# USB_SATA.net
KiCad netlist of a schematic drawn in Altium Designer
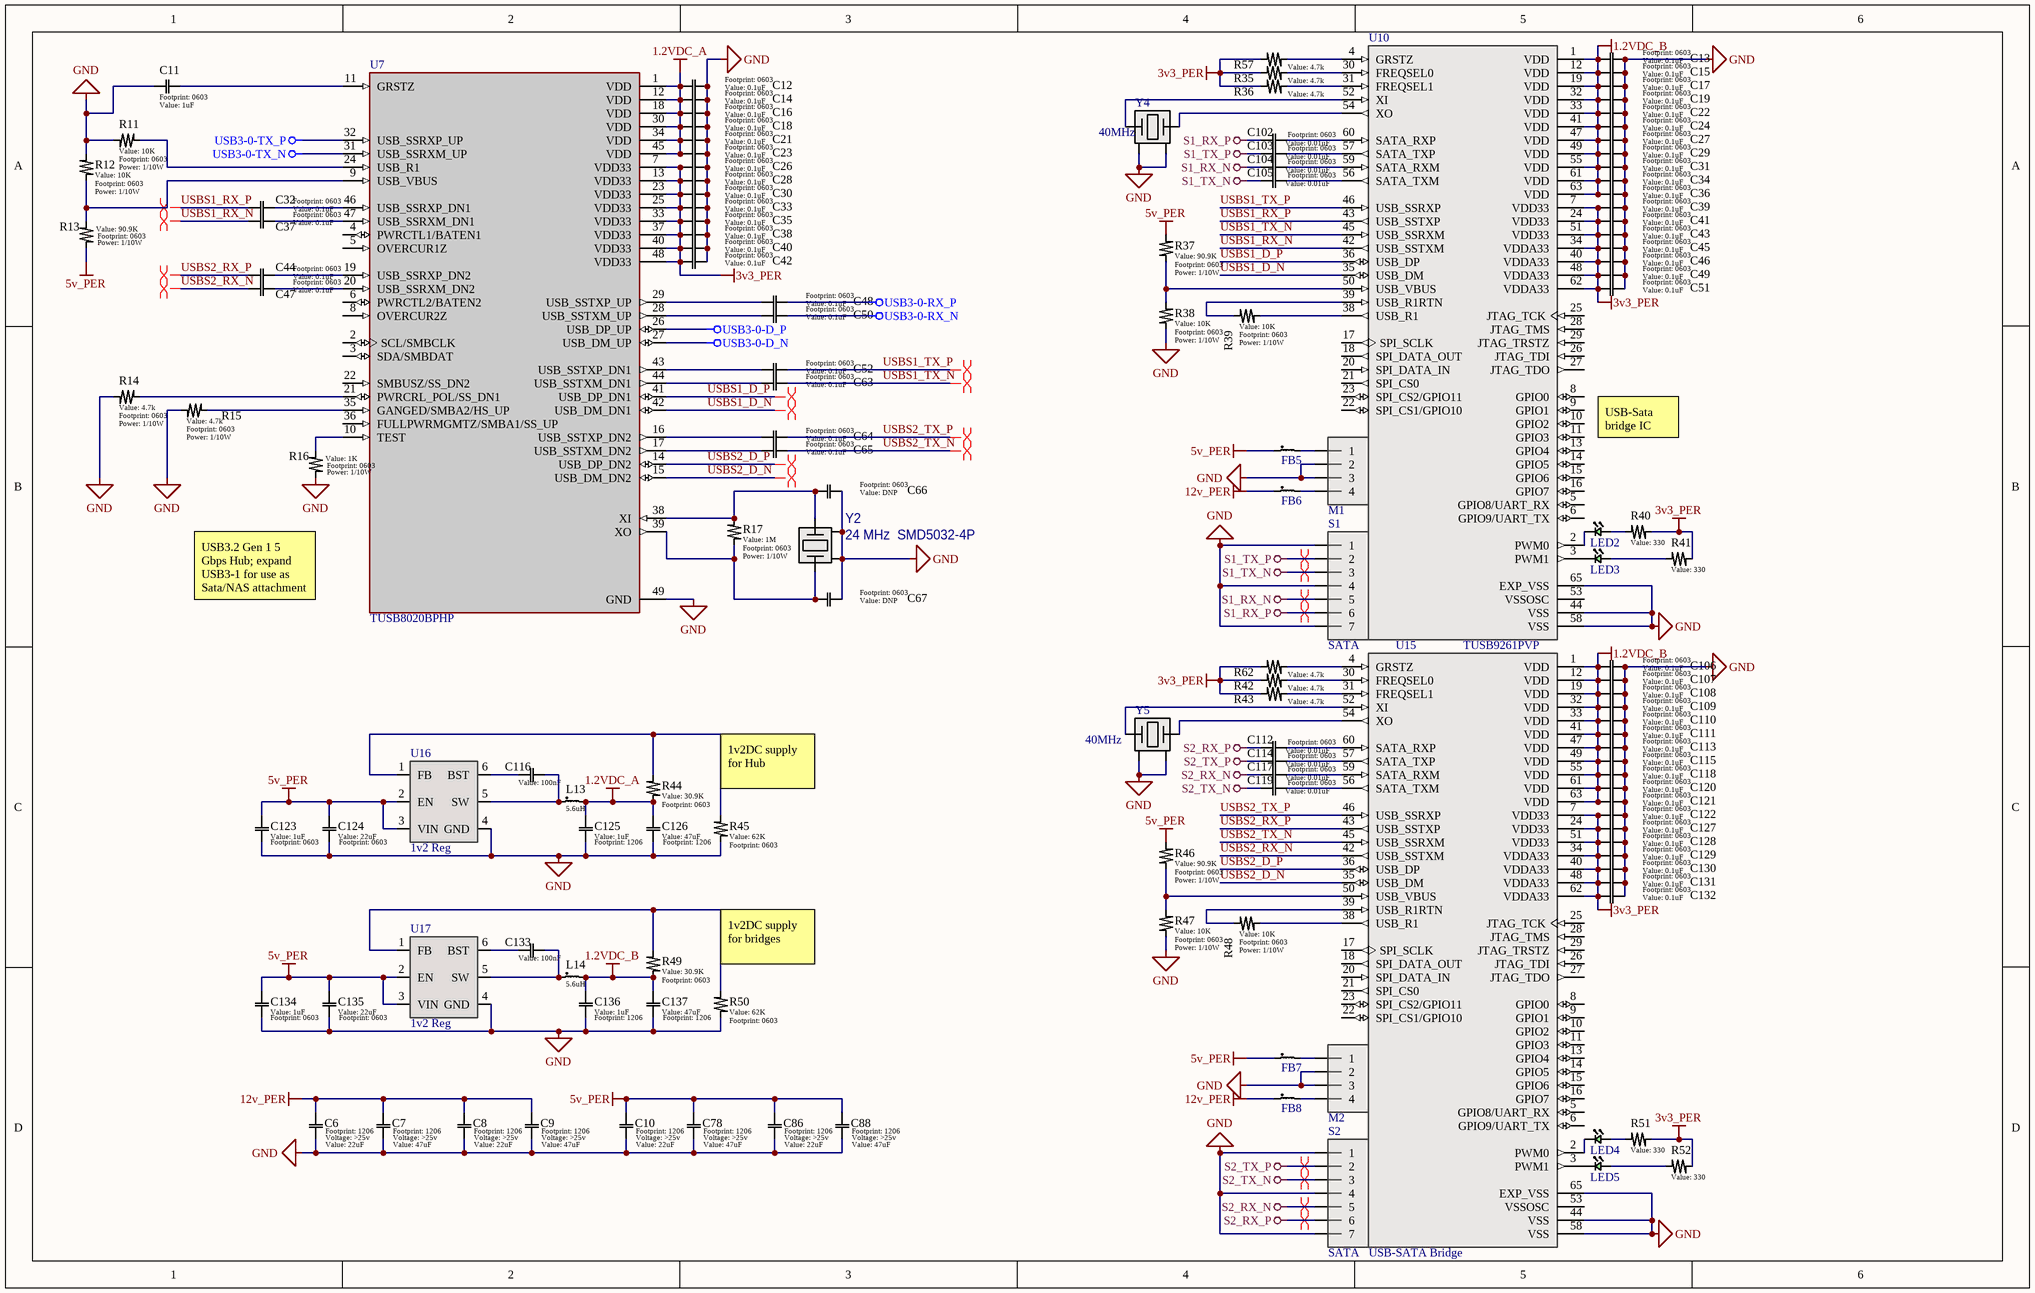
[diagram p0: USB_SATA.SchDoc]

(export (version "E")
  (design (tool "Eeschema 10.0.6"))
  (components
    (comp (ref "C6")
      (value "22uF")
      (footprint "1206")
      (fields
        (field (name "VOLTAGE") ">25v")
        (field (name "TOLERANCE") "20%")
        (field (name "Comment") "Generic Capacitor")
      )
      (libsource (lib "Capacitors") (part "Generic Capacitor"))
    )
    (comp (ref "C7")
      (value "47uF")
      (footprint "1206")
      (fields
        (field (name "VOLTAGE") ">25v")
        (field (name "TOLERANCE") "20%")
        (field (name "Comment") "Generic Capacitor")
      )
      (libsource (lib "Capacitors") (part "Generic Capacitor"))
    )
    (comp (ref "C8")
      (value "22uF")
      (footprint "1206")
      (fields
        (field (name "VOLTAGE") ">25v")
        (field (name "TOLERANCE") "20%")
        (field (name "Comment") "Generic Capacitor")
      )
      (libsource (lib "Capacitors") (part "Generic Capacitor"))
    )
    (comp (ref "C9")
      (value "47uF")
      (footprint "1206")
      (fields
        (field (name "VOLTAGE") ">25v")
        (field (name "TOLERANCE") "20%")
        (field (name "Comment") "Generic Capacitor")
      )
      (libsource (lib "Capacitors") (part "Generic Capacitor"))
    )
    (comp (ref "C10")
      (value "22uF")
      (footprint "1206")
      (fields
        (field (name "VOLTAGE") ">25v")
        (field (name "TOLERANCE") "20%")
        (field (name "Comment") "Generic Capacitor")
      )
      (libsource (lib "Capacitors") (part "Generic Capacitor"))
    )
    (comp (ref "C11")
      (value "1uF")
      (footprint "0603")
      (fields
        (field (name "VOLTAGE") ">10V")
        (field (name "TOLERANCE") "10%")
        (field (name "Comment") "Generic Capacitor")
      )
      (libsource (lib "Capacitors") (part "Generic Capacitor"))
    )
    (comp (ref "C12")
      (value "0.1uF")
      (footprint "0603")
      (fields
        (field (name "VOLTAGE") "10V")
        (field (name "TOLERANCE") "10%")
        (field (name "Comment") "Generic Capacitor")
      )
      (libsource (lib "Capacitors") (part "Generic Capacitor"))
    )
    (comp (ref "C13")
      (value "0.1uF")
      (footprint "0603")
      (fields
        (field (name "VOLTAGE") "10V")
        (field (name "TOLERANCE") "10%")
        (field (name "Comment") "Generic Capacitor")
      )
      (libsource (lib "Capacitors") (part "Generic Capacitor"))
    )
    (comp (ref "C14")
      (value "0.1uF")
      (footprint "0603")
      (fields
        (field (name "VOLTAGE") "10V")
        (field (name "TOLERANCE") "10%")
        (field (name "Comment") "Generic Capacitor")
      )
      (libsource (lib "Capacitors") (part "Generic Capacitor"))
    )
    (comp (ref "C15")
      (value "0.1uF")
      (footprint "0603")
      (fields
        (field (name "VOLTAGE") "10V")
        (field (name "TOLERANCE") "10%")
        (field (name "Comment") "Generic Capacitor")
      )
      (libsource (lib "Capacitors") (part "Generic Capacitor"))
    )
    (comp (ref "C16")
      (value "0.1uF")
      (footprint "0603")
      (fields
        (field (name "VOLTAGE") "10V")
        (field (name "TOLERANCE") "10%")
        (field (name "Comment") "Generic Capacitor")
      )
      (libsource (lib "Capacitors") (part "Generic Capacitor"))
    )
    (comp (ref "C17")
      (value "0.1uF")
      (footprint "0603")
      (fields
        (field (name "VOLTAGE") "10V")
        (field (name "TOLERANCE") "10%")
        (field (name "Comment") "Generic Capacitor")
      )
      (libsource (lib "Capacitors") (part "Generic Capacitor"))
    )
    (comp (ref "C18")
      (value "0.1uF")
      (footprint "0603")
      (fields
        (field (name "VOLTAGE") "10V")
        (field (name "TOLERANCE") "10%")
        (field (name "Comment") "Generic Capacitor")
      )
      (libsource (lib "Capacitors") (part "Generic Capacitor"))
    )
    (comp (ref "C19")
      (value "0.1uF")
      (footprint "0603")
      (fields
        (field (name "VOLTAGE") "10V")
        (field (name "TOLERANCE") "10%")
        (field (name "Comment") "Generic Capacitor")
      )
      (libsource (lib "Capacitors") (part "Generic Capacitor"))
    )
    (comp (ref "C21")
      (value "0.1uF")
      (footprint "0603")
      (fields
        (field (name "VOLTAGE") "10V")
        (field (name "TOLERANCE") "10%")
        (field (name "Comment") "Generic Capacitor")
      )
      (libsource (lib "Capacitors") (part "Generic Capacitor"))
    )
    (comp (ref "C22")
      (value "0.1uF")
      (footprint "0603")
      (fields
        (field (name "VOLTAGE") "10V")
        (field (name "TOLERANCE") "10%")
        (field (name "Comment") "Generic Capacitor")
      )
      (libsource (lib "Capacitors") (part "Generic Capacitor"))
    )
    (comp (ref "C23")
      (value "0.1uF")
      (footprint "0603")
      (fields
        (field (name "VOLTAGE") "10V")
        (field (name "TOLERANCE") "10%")
        (field (name "Comment") "Generic Capacitor")
      )
      (libsource (lib "Capacitors") (part "Generic Capacitor"))
    )
    (comp (ref "C24")
      (value "0.1uF")
      (footprint "0603")
      (fields
        (field (name "VOLTAGE") "10V")
        (field (name "TOLERANCE") "10%")
        (field (name "Comment") "Generic Capacitor")
      )
      (libsource (lib "Capacitors") (part "Generic Capacitor"))
    )
    (comp (ref "C26")
      (value "0.1uF")
      (footprint "0603")
      (fields
        (field (name "VOLTAGE") "10V")
        (field (name "TOLERANCE") "10%")
        (field (name "Comment") "Generic Capacitor")
      )
      (libsource (lib "Capacitors") (part "Generic Capacitor"))
    )
    (comp (ref "C27")
      (value "0.1uF")
      (footprint "0603")
      (fields
        (field (name "VOLTAGE") "10V")
        (field (name "TOLERANCE") "10%")
        (field (name "Comment") "Generic Capacitor")
      )
      (libsource (lib "Capacitors") (part "Generic Capacitor"))
    )
    (comp (ref "C28")
      (value "0.1uF")
      (footprint "0603")
      (fields
        (field (name "VOLTAGE") "10V")
        (field (name "TOLERANCE") "10%")
        (field (name "Comment") "Generic Capacitor")
      )
      (libsource (lib "Capacitors") (part "Generic Capacitor"))
    )
    (comp (ref "C29")
      (value "0.1uF")
      (footprint "0603")
      (fields
        (field (name "VOLTAGE") "10V")
        (field (name "TOLERANCE") "10%")
        (field (name "Comment") "Generic Capacitor")
      )
      (libsource (lib "Capacitors") (part "Generic Capacitor"))
    )
    (comp (ref "C30")
      (value "0.1uF")
      (footprint "0603")
      (fields
        (field (name "VOLTAGE") "10V")
        (field (name "TOLERANCE") "10%")
        (field (name "Comment") "Generic Capacitor")
      )
      (libsource (lib "Capacitors") (part "Generic Capacitor"))
    )
    (comp (ref "C31")
      (value "0.1uF")
      (footprint "0603")
      (fields
        (field (name "VOLTAGE") "10V")
        (field (name "TOLERANCE") "10%")
        (field (name "Comment") "Generic Capacitor")
      )
      (libsource (lib "Capacitors") (part "Generic Capacitor"))
    )
    (comp (ref "C32")
      (value "0.1uF")
      (footprint "0603")
      (fields
        (field (name "VOLTAGE") "10V")
        (field (name "TOLERANCE") "10%")
        (field (name "Comment") "Generic Capacitor")
      )
      (libsource (lib "Capacitors") (part "Generic Capacitor"))
    )
    (comp (ref "C33")
      (value "0.1uF")
      (footprint "0603")
      (fields
        (field (name "VOLTAGE") "10V")
        (field (name "TOLERANCE") "10%")
        (field (name "Comment") "Generic Capacitor")
      )
      (libsource (lib "Capacitors") (part "Generic Capacitor"))
    )
    (comp (ref "C34")
      (value "0.1uF")
      (footprint "0603")
      (fields
        (field (name "VOLTAGE") "10V")
        (field (name "TOLERANCE") "10%")
        (field (name "Comment") "Generic Capacitor")
      )
      (libsource (lib "Capacitors") (part "Generic Capacitor"))
    )
    (comp (ref "C35")
      (value "0.1uF")
      (footprint "0603")
      (fields
        (field (name "VOLTAGE") "10V")
        (field (name "TOLERANCE") "10%")
        (field (name "Comment") "Generic Capacitor")
      )
      (libsource (lib "Capacitors") (part "Generic Capacitor"))
    )
    (comp (ref "C36")
      (value "0.1uF")
      (footprint "0603")
      (fields
        (field (name "VOLTAGE") "10V")
        (field (name "TOLERANCE") "10%")
        (field (name "Comment") "Generic Capacitor")
      )
      (libsource (lib "Capacitors") (part "Generic Capacitor"))
    )
    (comp (ref "C37")
      (value "0.1uF")
      (footprint "0603")
      (fields
        (field (name "VOLTAGE") "10V")
        (field (name "TOLERANCE") "10%")
        (field (name "Comment") "Generic Capacitor")
      )
      (libsource (lib "Capacitors") (part "Generic Capacitor"))
    )
    (comp (ref "C38")
      (value "0.1uF")
      (footprint "0603")
      (fields
        (field (name "VOLTAGE") "10V")
        (field (name "TOLERANCE") "10%")
        (field (name "Comment") "Generic Capacitor")
      )
      (libsource (lib "Capacitors") (part "Generic Capacitor"))
    )
    (comp (ref "C39")
      (value "0.1uF")
      (footprint "0603")
      (fields
        (field (name "VOLTAGE") "10V")
        (field (name "TOLERANCE") "10%")
        (field (name "Comment") "Generic Capacitor")
      )
      (libsource (lib "Capacitors") (part "Generic Capacitor"))
    )
    (comp (ref "C40")
      (value "0.1uF")
      (footprint "0603")
      (fields
        (field (name "VOLTAGE") "10V")
        (field (name "TOLERANCE") "10%")
        (field (name "Comment") "Generic Capacitor")
      )
      (libsource (lib "Capacitors") (part "Generic Capacitor"))
    )
    (comp (ref "C41")
      (value "0.1uF")
      (footprint "0603")
      (fields
        (field (name "VOLTAGE") "10V")
        (field (name "TOLERANCE") "10%")
        (field (name "Comment") "Generic Capacitor")
      )
      (libsource (lib "Capacitors") (part "Generic Capacitor"))
    )
    (comp (ref "C42")
      (value "0.1uF")
      (footprint "0603")
      (fields
        (field (name "VOLTAGE") "10V")
        (field (name "TOLERANCE") "10%")
        (field (name "Comment") "Generic Capacitor")
      )
      (libsource (lib "Capacitors") (part "Generic Capacitor"))
    )
    (comp (ref "C43")
      (value "0.1uF")
      (footprint "0603")
      (fields
        (field (name "VOLTAGE") "10V")
        (field (name "TOLERANCE") "10%")
        (field (name "Comment") "Generic Capacitor")
      )
      (libsource (lib "Capacitors") (part "Generic Capacitor"))
    )
    (comp (ref "C44")
      (value "0.1uF")
      (footprint "0603")
      (fields
        (field (name "VOLTAGE") "10V")
        (field (name "TOLERANCE") "10%")
        (field (name "Comment") "Generic Capacitor")
      )
      (libsource (lib "Capacitors") (part "Generic Capacitor"))
    )
    (comp (ref "C45")
      (value "0.1uF")
      (footprint "0603")
      (fields
        (field (name "VOLTAGE") "10V")
        (field (name "TOLERANCE") "10%")
        (field (name "Comment") "Generic Capacitor")
      )
      (libsource (lib "Capacitors") (part "Generic Capacitor"))
    )
    (comp (ref "C46")
      (value "0.1uF")
      (footprint "0603")
      (fields
        (field (name "VOLTAGE") "10V")
        (field (name "TOLERANCE") "10%")
        (field (name "Comment") "Generic Capacitor")
      )
      (libsource (lib "Capacitors") (part "Generic Capacitor"))
    )
    (comp (ref "C47")
      (value "0.1uF")
      (footprint "0603")
      (fields
        (field (name "VOLTAGE") "10V")
        (field (name "TOLERANCE") "10%")
        (field (name "Comment") "Generic Capacitor")
      )
      (libsource (lib "Capacitors") (part "Generic Capacitor"))
    )
    (comp (ref "C48")
      (value "0.1uF")
      (footprint "0603")
      (fields
        (field (name "VOLTAGE") "10V")
        (field (name "TOLERANCE") "10%")
        (field (name "Comment") "Generic Capacitor")
      )
      (libsource (lib "Capacitors") (part "Generic Capacitor"))
    )
    (comp (ref "C49")
      (value "0.1uF")
      (footprint "0603")
      (fields
        (field (name "VOLTAGE") "10V")
        (field (name "TOLERANCE") "10%")
        (field (name "Comment") "Generic Capacitor")
      )
      (libsource (lib "Capacitors") (part "Generic Capacitor"))
    )
    (comp (ref "C50")
      (value "0.1uF")
      (footprint "0603")
      (fields
        (field (name "VOLTAGE") "10V")
        (field (name "TOLERANCE") "10%")
        (field (name "Comment") "Generic Capacitor")
      )
      (libsource (lib "Capacitors") (part "Generic Capacitor"))
    )
    (comp (ref "C51")
      (value "0.1uF")
      (footprint "0603")
      (fields
        (field (name "VOLTAGE") "10V")
        (field (name "TOLERANCE") "10%")
        (field (name "Comment") "Generic Capacitor")
      )
      (libsource (lib "Capacitors") (part "Generic Capacitor"))
    )
    (comp (ref "C52")
      (value "0.1uF")
      (footprint "0603")
      (fields
        (field (name "VOLTAGE") "10V")
        (field (name "TOLERANCE") "10%")
        (field (name "Comment") "Generic Capacitor")
      )
      (libsource (lib "Capacitors") (part "Generic Capacitor"))
    )
    (comp (ref "C63")
      (value "0.1uF")
      (footprint "0603")
      (fields
        (field (name "VOLTAGE") "10V")
        (field (name "TOLERANCE") "10%")
        (field (name "Comment") "Generic Capacitor")
      )
      (libsource (lib "Capacitors") (part "Generic Capacitor"))
    )
    (comp (ref "C64")
      (value "0.1uF")
      (footprint "0603")
      (fields
        (field (name "VOLTAGE") "10V")
        (field (name "TOLERANCE") "10%")
        (field (name "Comment") "Generic Capacitor")
      )
      (libsource (lib "Capacitors") (part "Generic Capacitor"))
    )
    (comp (ref "C65")
      (value "0.1uF")
      (footprint "0603")
      (fields
        (field (name "VOLTAGE") "10V")
        (field (name "TOLERANCE") "10%")
        (field (name "Comment") "Generic Capacitor")
      )
      (libsource (lib "Capacitors") (part "Generic Capacitor"))
    )
    (comp (ref "C66")
      (value "DNP")
      (footprint "0603")
      (fields
        (field (name "VOLTAGE") ">10V")
        (field (name "TOLERANCE") "10%")
        (field (name "Comment") "Generic Capacitor")
      )
      (libsource (lib "Capacitors") (part "Generic Capacitor"))
    )
    (comp (ref "C67")
      (value "DNP")
      (footprint "0603")
      (fields
        (field (name "VOLTAGE") ">10V")
        (field (name "TOLERANCE") "10%")
        (field (name "Comment") "Generic Capacitor")
      )
      (libsource (lib "Capacitors") (part "Generic Capacitor"))
    )
    (comp (ref "C78")
      (value "47uF")
      (footprint "1206")
      (fields
        (field (name "VOLTAGE") ">25v")
        (field (name "TOLERANCE") "20%")
        (field (name "Comment") "Generic Capacitor")
      )
      (libsource (lib "Capacitors") (part "Generic Capacitor"))
    )
    (comp (ref "C86")
      (value "22uF")
      (footprint "1206")
      (fields
        (field (name "VOLTAGE") ">25v")
        (field (name "TOLERANCE") "20%")
        (field (name "Comment") "Generic Capacitor")
      )
      (libsource (lib "Capacitors") (part "Generic Capacitor"))
    )
    (comp (ref "C88")
      (value "47uF")
      (footprint "1206")
      (fields
        (field (name "VOLTAGE") ">25v")
        (field (name "TOLERANCE") "20%")
        (field (name "Comment") "Generic Capacitor")
      )
      (libsource (lib "Capacitors") (part "Generic Capacitor"))
    )
    (comp (ref "C102")
      (value "0.01uF")
      (footprint "0603")
      (fields
        (field (name "VOLTAGE") "10V")
        (field (name "TOLERANCE") "10%")
        (field (name "Comment") "Generic Capacitor")
      )
      (libsource (lib "Capacitors") (part "Generic Capacitor"))
    )
    (comp (ref "C103")
      (value "0.01uF")
      (footprint "0603")
      (fields
        (field (name "VOLTAGE") "10V")
        (field (name "TOLERANCE") "10%")
        (field (name "Comment") "Generic Capacitor")
      )
      (libsource (lib "Capacitors") (part "Generic Capacitor"))
    )
    (comp (ref "C104")
      (value "0.01uF")
      (footprint "0603")
      (fields
        (field (name "VOLTAGE") "10V")
        (field (name "TOLERANCE") "10%")
        (field (name "Comment") "Generic Capacitor")
      )
      (libsource (lib "Capacitors") (part "Generic Capacitor"))
    )
    (comp (ref "C105")
      (value "0.01uF")
      (footprint "0603")
      (fields
        (field (name "VOLTAGE") "10V")
        (field (name "TOLERANCE") "10%")
        (field (name "Comment") "Generic Capacitor")
      )
      (libsource (lib "Capacitors") (part "Generic Capacitor"))
    )
    (comp (ref "C106")
      (value "0.1uF")
      (footprint "0603")
      (fields
        (field (name "VOLTAGE") "10V")
        (field (name "TOLERANCE") "10%")
        (field (name "Comment") "Generic Capacitor")
      )
      (libsource (lib "Capacitors") (part "Generic Capacitor"))
    )
    (comp (ref "C107")
      (value "0.1uF")
      (footprint "0603")
      (fields
        (field (name "VOLTAGE") "10V")
        (field (name "TOLERANCE") "10%")
        (field (name "Comment") "Generic Capacitor")
      )
      (libsource (lib "Capacitors") (part "Generic Capacitor"))
    )
    (comp (ref "C108")
      (value "0.1uF")
      (footprint "0603")
      (fields
        (field (name "VOLTAGE") "10V")
        (field (name "TOLERANCE") "10%")
        (field (name "Comment") "Generic Capacitor")
      )
      (libsource (lib "Capacitors") (part "Generic Capacitor"))
    )
    (comp (ref "C109")
      (value "0.1uF")
      (footprint "0603")
      (fields
        (field (name "VOLTAGE") "10V")
        (field (name "TOLERANCE") "10%")
        (field (name "Comment") "Generic Capacitor")
      )
      (libsource (lib "Capacitors") (part "Generic Capacitor"))
    )
    (comp (ref "C110")
      (value "0.1uF")
      (footprint "0603")
      (fields
        (field (name "VOLTAGE") "10V")
        (field (name "TOLERANCE") "10%")
        (field (name "Comment") "Generic Capacitor")
      )
      (libsource (lib "Capacitors") (part "Generic Capacitor"))
    )
    (comp (ref "C111")
      (value "0.1uF")
      (footprint "0603")
      (fields
        (field (name "VOLTAGE") "10V")
        (field (name "TOLERANCE") "10%")
        (field (name "Comment") "Generic Capacitor")
      )
      (libsource (lib "Capacitors") (part "Generic Capacitor"))
    )
    (comp (ref "C112")
      (value "0.01uF")
      (footprint "0603")
      (fields
        (field (name "VOLTAGE") "10V")
        (field (name "TOLERANCE") "10%")
        (field (name "Comment") "Generic Capacitor")
      )
      (libsource (lib "Capacitors") (part "Generic Capacitor"))
    )
    (comp (ref "C113")
      (value "0.1uF")
      (footprint "0603")
      (fields
        (field (name "VOLTAGE") "10V")
        (field (name "TOLERANCE") "10%")
        (field (name "Comment") "Generic Capacitor")
      )
      (libsource (lib "Capacitors") (part "Generic Capacitor"))
    )
    (comp (ref "C114")
      (value "0.01uF")
      (footprint "0603")
      (fields
        (field (name "VOLTAGE") "10V")
        (field (name "TOLERANCE") "10%")
        (field (name "Comment") "Generic Capacitor")
      )
      (libsource (lib "Capacitors") (part "Generic Capacitor"))
    )
    (comp (ref "C115")
      (value "0.1uF")
      (footprint "0603")
      (fields
        (field (name "VOLTAGE") "10V")
        (field (name "TOLERANCE") "10%")
        (field (name "Comment") "Generic Capacitor")
      )
      (libsource (lib "Capacitors") (part "Generic Capacitor"))
    )
    (comp (ref "C116")
      (value "100nF")
      (footprint "0603")
      (fields
        (field (name "VOLTAGE") ">10V")
        (field (name "TOLERANCE") "10%")
        (field (name "Comment") "Generic Capacitor")
      )
      (libsource (lib "Capacitors") (part "Generic Capacitor"))
    )
    (comp (ref "C117")
      (value "0.01uF")
      (footprint "0603")
      (fields
        (field (name "VOLTAGE") "10V")
        (field (name "TOLERANCE") "10%")
        (field (name "Comment") "Generic Capacitor")
      )
      (libsource (lib "Capacitors") (part "Generic Capacitor"))
    )
    (comp (ref "C118")
      (value "0.1uF")
      (footprint "0603")
      (fields
        (field (name "VOLTAGE") "10V")
        (field (name "TOLERANCE") "10%")
        (field (name "Comment") "Generic Capacitor")
      )
      (libsource (lib "Capacitors") (part "Generic Capacitor"))
    )
    (comp (ref "C119")
      (value "0.01uF")
      (footprint "0603")
      (fields
        (field (name "VOLTAGE") "10V")
        (field (name "TOLERANCE") "10%")
        (field (name "Comment") "Generic Capacitor")
      )
      (libsource (lib "Capacitors") (part "Generic Capacitor"))
    )
    (comp (ref "C120")
      (value "0.1uF")
      (footprint "0603")
      (fields
        (field (name "VOLTAGE") "10V")
        (field (name "TOLERANCE") "10%")
        (field (name "Comment") "Generic Capacitor")
      )
      (libsource (lib "Capacitors") (part "Generic Capacitor"))
    )
    (comp (ref "C121")
      (value "0.1uF")
      (footprint "0603")
      (fields
        (field (name "VOLTAGE") "10V")
        (field (name "TOLERANCE") "10%")
        (field (name "Comment") "Generic Capacitor")
      )
      (libsource (lib "Capacitors") (part "Generic Capacitor"))
    )
    (comp (ref "C122")
      (value "0.1uF")
      (footprint "0603")
      (fields
        (field (name "VOLTAGE") "10V")
        (field (name "TOLERANCE") "10%")
        (field (name "Comment") "Generic Capacitor")
      )
      (libsource (lib "Capacitors") (part "Generic Capacitor"))
    )
    (comp (ref "C123")
      (value "1uF")
      (footprint "0603")
      (fields
        (field (name "VOLTAGE") ">10V")
        (field (name "TOLERANCE") "10%")
        (field (name "Comment") "Generic Capacitor")
      )
      (libsource (lib "Capacitors") (part "Generic Capacitor"))
    )
    (comp (ref "C124")
      (value "22uF")
      (footprint "0603")
      (fields
        (field (name "VOLTAGE") ">10V")
        (field (name "TOLERANCE") "10%")
        (field (name "Comment") "Generic Capacitor")
      )
      (libsource (lib "Capacitors") (part "Generic Capacitor"))
    )
    (comp (ref "C125")
      (value "1uF")
      (footprint "1206")
      (fields
        (field (name "VOLTAGE") ">10V")
        (field (name "TOLERANCE") "10%")
        (field (name "Comment") "Generic Capacitor")
      )
      (libsource (lib "Capacitors") (part "Generic Capacitor"))
    )
    (comp (ref "C126")
      (value "47uF")
      (footprint "1206")
      (fields
        (field (name "VOLTAGE") ">10V")
        (field (name "TOLERANCE") "10%")
        (field (name "Comment") "Generic Capacitor")
      )
      (libsource (lib "Capacitors") (part "Generic Capacitor"))
    )
    (comp (ref "C127")
      (value "0.1uF")
      (footprint "0603")
      (fields
        (field (name "VOLTAGE") "10V")
        (field (name "TOLERANCE") "10%")
        (field (name "Comment") "Generic Capacitor")
      )
      (libsource (lib "Capacitors") (part "Generic Capacitor"))
    )
    (comp (ref "C128")
      (value "0.1uF")
      (footprint "0603")
      (fields
        (field (name "VOLTAGE") "10V")
        (field (name "TOLERANCE") "10%")
        (field (name "Comment") "Generic Capacitor")
      )
      (libsource (lib "Capacitors") (part "Generic Capacitor"))
    )
    (comp (ref "C129")
      (value "0.1uF")
      (footprint "0603")
      (fields
        (field (name "VOLTAGE") "10V")
        (field (name "TOLERANCE") "10%")
        (field (name "Comment") "Generic Capacitor")
      )
      (libsource (lib "Capacitors") (part "Generic Capacitor"))
    )
    (comp (ref "C130")
      (value "0.1uF")
      (footprint "0603")
      (fields
        (field (name "VOLTAGE") "10V")
        (field (name "TOLERANCE") "10%")
        (field (name "Comment") "Generic Capacitor")
      )
      (libsource (lib "Capacitors") (part "Generic Capacitor"))
    )
    (comp (ref "C131")
      (value "0.1uF")
      (footprint "0603")
      (fields
        (field (name "VOLTAGE") "10V")
        (field (name "TOLERANCE") "10%")
        (field (name "Comment") "Generic Capacitor")
      )
      (libsource (lib "Capacitors") (part "Generic Capacitor"))
    )
    (comp (ref "C132")
      (value "0.1uF")
      (footprint "0603")
      (fields
        (field (name "VOLTAGE") "10V")
        (field (name "TOLERANCE") "10%")
        (field (name "Comment") "Generic Capacitor")
      )
      (libsource (lib "Capacitors") (part "Generic Capacitor"))
    )
    (comp (ref "C133")
      (value "100nF")
      (footprint "0603")
      (fields
        (field (name "VOLTAGE") ">10V")
        (field (name "TOLERANCE") "10%")
        (field (name "Comment") "Generic Capacitor")
      )
      (libsource (lib "Capacitors") (part "Generic Capacitor"))
    )
    (comp (ref "C134")
      (value "1uF")
      (footprint "0603")
      (fields
        (field (name "VOLTAGE") ">10V")
        (field (name "TOLERANCE") "10%")
        (field (name "Comment") "Generic Capacitor")
      )
      (libsource (lib "Capacitors") (part "Generic Capacitor"))
    )
    (comp (ref "C135")
      (value "22uF")
      (footprint "0603")
      (fields
        (field (name "VOLTAGE") ">10V")
        (field (name "TOLERANCE") "10%")
        (field (name "Comment") "Generic Capacitor")
      )
      (libsource (lib "Capacitors") (part "Generic Capacitor"))
    )
    (comp (ref "C136")
      (value "1uF")
      (footprint "1206")
      (fields
        (field (name "VOLTAGE") ">10V")
        (field (name "TOLERANCE") "10%")
        (field (name "Comment") "Generic Capacitor")
      )
      (libsource (lib "Capacitors") (part "Generic Capacitor"))
    )
    (comp (ref "C137")
      (value "47uF")
      (footprint "1206")
      (fields
        (field (name "VOLTAGE") ">10V")
        (field (name "TOLERANCE") "10%")
        (field (name "Comment") "Generic Capacitor")
      )
      (libsource (lib "Capacitors") (part "Generic Capacitor"))
    )
    (comp (ref "FB5")
      (value "1206 Ferrite")
      (footprint "1206")
      (description "160 Ohms @ 100MHz 1 Power, Signal Line Ferrite Bead 1206 (3216 Metric) 6A 18mOhm")
      (libsource (lib "Inductors") (part "HI1206T161R-10"))
    )
    (comp (ref "FB6")
      (value "1206 Ferrite")
      (footprint "1206")
      (description "160 Ohms @ 100MHz 1 Power, Signal Line Ferrite Bead 1206 (3216 Metric) 6A 18mOhm")
      (libsource (lib "Inductors") (part "HI1206T161R-10"))
    )
    (comp (ref "FB7")
      (value "1206 Ferrite")
      (footprint "1206")
      (description "160 Ohms @ 100MHz 1 Power, Signal Line Ferrite Bead 1206 (3216 Metric) 6A 18mOhm")
      (libsource (lib "Inductors") (part "HI1206T161R-10"))
    )
    (comp (ref "FB8")
      (value "1206 Ferrite")
      (footprint "1206")
      (description "160 Ohms @ 100MHz 1 Power, Signal Line Ferrite Bead 1206 (3216 Metric) 6A 18mOhm")
      (libsource (lib "Inductors") (part "HI1206T161R-10"))
    )
    (comp (ref "L13")
      (value "5.6uH")
      (footprint "TMPC0402HP")
      (description "2A 5.6uH ±20% SMD Power Inductor")
      (libsource (lib "Inductors") (part "TMPC0402HP-5R6MG-Z02"))
    )
    (comp (ref "L14")
      (value "5.6uH")
      (footprint "TMPC0402HP")
      (description "2A 5.6uH ±20% SMD Power Inductor")
      (libsource (lib "Inductors") (part "TMPC0402HP-5R6MG-Z02"))
    )
    (comp (ref "LED2")
      (value "LTST-C191KGKT")
      (footprint "0603 (1608 Metric) Concave")
      (description "LED Uni-Color Green 574nm 2-Pin Chip LED T/R")
      (libsource (lib "Gamber - Johnson LLC") (part "LTST-C191KGKT"))
    )
    (comp (ref "LED3")
      (value "LTST-C191KGKT")
      (footprint "0603 (1608 Metric) Concave")
      (description "LED Uni-Color Green 574nm 2-Pin Chip LED T/R")
      (libsource (lib "Gamber - Johnson LLC") (part "LTST-C191KGKT"))
    )
    (comp (ref "LED4")
      (value "LTST-C191KGKT")
      (footprint "0603 (1608 Metric) Concave")
      (description "LED Uni-Color Green 574nm 2-Pin Chip LED T/R")
      (libsource (lib "Gamber - Johnson LLC") (part "LTST-C191KGKT"))
    )
    (comp (ref "LED5")
      (value "LTST-C191KGKT")
      (footprint "0603 (1608 Metric) Concave")
      (description "LED Uni-Color Green 574nm 2-Pin Chip LED T/R")
      (libsource (lib "Gamber - Johnson LLC") (part "LTST-C191KGKT"))
    )
    (comp (ref "M1")
      (value "MATE-n-Lock")
      (footprint "794287-1")
      (description "4 Position Header Connector 0.200\" (5.08mm) Through Hole Tin")
      (libsource (lib "Connectors") (part "794287-1"))
    )
    (comp (ref "M2")
      (value "MATE-n-Lock")
      (footprint "794287-1")
      (description "4 Position Header Connector 0.200\" (5.08mm) Through Hole Tin")
      (libsource (lib "Connectors") (part "794287-1"))
    )
    (comp (ref "R11")
      (value "10K")
      (footprint "0603")
      (fields
        (field (name "TOLERANCE") "1%")
        (field (name "POWER") "1/10W")
        (field (name "Comment") "Generic Resistor")
      )
      (libsource (lib "Resistors") (part "Generic Resistor"))
    )
    (comp (ref "R12")
      (value "10K")
      (footprint "0603")
      (fields
        (field (name "TOLERANCE") "1%")
        (field (name "POWER") "1/10W")
        (field (name "Comment") "Generic Resistor")
      )
      (libsource (lib "Resistors") (part "Generic Resistor"))
    )
    (comp (ref "R13")
      (value "90.9K")
      (footprint "0603")
      (fields
        (field (name "TOLERANCE") "1%")
        (field (name "POWER") "1/10W")
        (field (name "Comment") "Generic Resistor")
      )
      (libsource (lib "Resistors") (part "Generic Resistor"))
    )
    (comp (ref "R14")
      (value "4.7k")
      (footprint "0603")
      (fields
        (field (name "TOLERANCE") "1%")
        (field (name "POWER") "1/10W")
        (field (name "Comment") "Generic Resistor")
      )
      (libsource (lib "Resistors") (part "Generic Resistor"))
    )
    (comp (ref "R15")
      (value "4.7k")
      (footprint "0603")
      (fields
        (field (name "TOLERANCE") "1%")
        (field (name "POWER") "1/10W")
        (field (name "Comment") "Generic Resistor")
      )
      (libsource (lib "Resistors") (part "Generic Resistor"))
    )
    (comp (ref "R16")
      (value "1K")
      (footprint "0603")
      (fields
        (field (name "TOLERANCE") "1%")
        (field (name "POWER") "1/10W")
        (field (name "Comment") "Generic Resistor")
      )
      (libsource (lib "Resistors") (part "Generic Resistor"))
    )
    (comp (ref "R17")
      (value "1M")
      (footprint "0603")
      (fields
        (field (name "TOLERANCE") "1%")
        (field (name "POWER") "1/10W")
        (field (name "Comment") "Generic Resistor")
      )
      (libsource (lib "Resistors") (part "Generic Resistor"))
    )
    (comp (ref "R35")
      (value "4.7k")
      (footprint "0603")
      (fields
        (field (name "TOLERANCE") "1%")
        (field (name "POWER") "1/10W")
        (field (name "Comment") "Generic Resistor")
      )
      (libsource (lib "Resistors") (part "Generic Resistor"))
    )
    (comp (ref "R36")
      (value "4.7k")
      (footprint "0603")
      (fields
        (field (name "TOLERANCE") "1%")
        (field (name "POWER") "1/10W")
        (field (name "Comment") "Generic Resistor")
      )
      (libsource (lib "Resistors") (part "Generic Resistor"))
    )
    (comp (ref "R37")
      (value "90.9K")
      (footprint "0603")
      (fields
        (field (name "TOLERANCE") "1%")
        (field (name "POWER") "1/10W")
        (field (name "Comment") "Generic Resistor")
      )
      (libsource (lib "Resistors") (part "Generic Resistor"))
    )
    (comp (ref "R38")
      (value "10K")
      (footprint "0603")
      (fields
        (field (name "TOLERANCE") "1%")
        (field (name "POWER") "1/10W")
        (field (name "Comment") "Generic Resistor")
      )
      (libsource (lib "Resistors") (part "Generic Resistor"))
    )
    (comp (ref "R39")
      (value "10K")
      (footprint "0603")
      (fields
        (field (name "TOLERANCE") "1%")
        (field (name "POWER") "1/10W")
        (field (name "Comment") "Generic Resistor")
      )
      (libsource (lib "Resistors") (part "Generic Resistor"))
    )
    (comp (ref "R40")
      (value "330")
      (footprint "0603")
      (fields
        (field (name "TOLERANCE") "1%")
        (field (name "POWER") "1/10W")
        (field (name "Comment") "Generic Resistor")
      )
      (libsource (lib "Resistors") (part "Generic Resistor"))
    )
    (comp (ref "R41")
      (value "330")
      (footprint "0603")
      (fields
        (field (name "TOLERANCE") "1%")
        (field (name "POWER") "1/10W")
        (field (name "Comment") "Generic Resistor")
      )
      (libsource (lib "Resistors") (part "Generic Resistor"))
    )
    (comp (ref "R42")
      (value "4.7k")
      (footprint "0603")
      (fields
        (field (name "TOLERANCE") "1%")
        (field (name "POWER") "1/10W")
        (field (name "Comment") "Generic Resistor")
      )
      (libsource (lib "Resistors") (part "Generic Resistor"))
    )
    (comp (ref "R43")
      (value "4.7k")
      (footprint "0603")
      (fields
        (field (name "TOLERANCE") "1%")
        (field (name "POWER") "1/10W")
        (field (name "Comment") "Generic Resistor")
      )
      (libsource (lib "Resistors") (part "Generic Resistor"))
    )
    (comp (ref "R44")
      (value "30.9K")
      (footprint "0603")
      (fields
        (field (name "TOLERANCE") "1%")
        (field (name "POWER") "1/10W")
        (field (name "Comment") "Generic Resistor")
      )
      (libsource (lib "Resistors") (part "Generic Resistor"))
    )
    (comp (ref "R45")
      (value "62K")
      (footprint "0603")
      (fields
        (field (name "TOLERANCE") "1%")
        (field (name "POWER") "1/10W")
        (field (name "Comment") "Generic Resistor")
      )
      (libsource (lib "Resistors") (part "Generic Resistor"))
    )
    (comp (ref "R46")
      (value "90.9K")
      (footprint "0603")
      (fields
        (field (name "TOLERANCE") "1%")
        (field (name "POWER") "1/10W")
        (field (name "Comment") "Generic Resistor")
      )
      (libsource (lib "Resistors") (part "Generic Resistor"))
    )
    (comp (ref "R47")
      (value "10K")
      (footprint "0603")
      (fields
        (field (name "TOLERANCE") "1%")
        (field (name "POWER") "1/10W")
        (field (name "Comment") "Generic Resistor")
      )
      (libsource (lib "Resistors") (part "Generic Resistor"))
    )
    (comp (ref "R48")
      (value "10K")
      (footprint "0603")
      (fields
        (field (name "TOLERANCE") "1%")
        (field (name "POWER") "1/10W")
        (field (name "Comment") "Generic Resistor")
      )
      (libsource (lib "Resistors") (part "Generic Resistor"))
    )
    (comp (ref "R49")
      (value "30.9K")
      (footprint "0603")
      (fields
        (field (name "TOLERANCE") "1%")
        (field (name "POWER") "1/10W")
        (field (name "Comment") "Generic Resistor")
      )
      (libsource (lib "Resistors") (part "Generic Resistor"))
    )
    (comp (ref "R50")
      (value "62K")
      (footprint "0603")
      (fields
        (field (name "TOLERANCE") "1%")
        (field (name "POWER") "1/10W")
        (field (name "Comment") "Generic Resistor")
      )
      (libsource (lib "Resistors") (part "Generic Resistor"))
    )
    (comp (ref "R51")
      (value "330")
      (footprint "0603")
      (fields
        (field (name "TOLERANCE") "1%")
        (field (name "POWER") "1/10W")
        (field (name "Comment") "Generic Resistor")
      )
      (libsource (lib "Resistors") (part "Generic Resistor"))
    )
    (comp (ref "R52")
      (value "330")
      (footprint "0603")
      (fields
        (field (name "TOLERANCE") "1%")
        (field (name "POWER") "1/10W")
        (field (name "Comment") "Generic Resistor")
      )
      (libsource (lib "Resistors") (part "Generic Resistor"))
    )
    (comp (ref "R57")
      (value "4.7k")
      (footprint "0603")
      (fields
        (field (name "TOLERANCE") "1%")
        (field (name "POWER") "1/10W")
        (field (name "Comment") "Generic Resistor")
      )
      (libsource (lib "Resistors") (part "Generic Resistor"))
    )
    (comp (ref "R62")
      (value "4.7k")
      (footprint "0603")
      (fields
        (field (name "TOLERANCE") "1%")
        (field (name "POWER") "1/10W")
        (field (name "Comment") "Generic Resistor")
      )
      (libsource (lib "Resistors") (part "Generic Resistor"))
    )
    (comp (ref "S1")
      (value "SATA")
      (footprint "67800-8025")
      (description "7 Position SATA Header, Shrouded Connector Solder Through Hole")
      (libsource (lib "Connectors") (part "67800-8025"))
    )
    (comp (ref "S2")
      (value "SATA")
      (footprint "67800-8025")
      (description "7 Position SATA Header, Shrouded Connector Solder Through Hole")
      (libsource (lib "Connectors") (part "67800-8025"))
    )
    (comp (ref "U7")
      (value "TUSB8020BPHP")
      (footprint "HTQFP-48(7x7)")
      (description "USB Hub Controller USB 3.0")
      (libsource (lib "Misc ICs") (part "TUSB8020BPHP"))
    )
    (comp (ref "U10")
      (value "USB-SATA Bridge")
      (footprint "64-HTQFP (7x7)")
      (description "HDD, CD, DVD Drive Interface 64-HTQFP _7x7_")
      (fields
        (field (name "MF") "Texas Instruments")
        (field (name "DIGI-KEY_PART_NUMBER") "296-28827-ND")
        (field (name "MP") "TUSB9261PVP")
      )
      (libsource (lib "Misc ICs") (part "TUSB9261PVP"))
    )
    (comp (ref "U15")
      (value "USB-SATA Bridge")
      (footprint "64-HTQFP (7x7)")
      (description "HDD, CD, DVD Drive Interface 64-HTQFP _7x7_")
      (fields (field (name "MF") "Texas Instruments") (field (name "DIGI-KEY_PART_NUMBER") "296-28827-ND"))
      (libsource (lib "Misc ICs") (part "TUSB9261PVP"))
    )
    (comp (ref "U16")
      (value "1v2 Reg")
      (footprint "TSOT-23-6")
      (description "Step-down type Adjustable 2A 1.2V~12V 3.8V~32V TSOT-23-6 DC-DC Converter")
      (libsource (lib "Regulators") (part "AP63201WU-7"))
    )
    (comp (ref "U17")
      (value "1v2 Reg")
      (footprint "TSOT-23-6")
      (description "Step-down type Adjustable 2A 1.2V~12V 3.8V~32V TSOT-23-6 DC-DC Converter")
      (libsource (lib "Regulators") (part "AP63201WU-7"))
    )
    (comp (ref "Y2")
      (value "24 MHz  SMD5032-4P")
      (footprint "ECS-240-18-30BQ-DS")
      (description "24 MHz ±30ppm Crystal 18pF 30 Ohms 4-SMD, No Lead")
      (libsource (lib "Gamber - Johnson LLC") (part "ECS-240-18-30BQ-DS"))
    )
    (comp (ref "Y4")
      (value "40MHz")
      (footprint "SMD3225-4P")
      (description "40MHz Surface Mount Crystal 10pF ±10ppm SMD3225-4P Crystal")
      (libsource (lib "Clock ICs") (part "L327S400H11L"))
    )
    (comp (ref "Y5")
      (value "40MHz")
      (footprint "SMD3225-4P")
      (description "40MHz Surface Mount Crystal 10pF ±10ppm SMD3225-4P Crystal")
      (libsource (lib "Clock ICs") (part "L327S400H11L"))
    )
  )
  (nets
    (net (code "1") (name "/USBS1_D_N") (class "Default")
      (node (ref "U10") (pin "35") (pinfunction "USB_DM_35") (pintype "bidirectional"))
      (node (ref "U7") (pin "42") (pinfunction "USB_DM_DN1_42") (pintype "bidirectional"))
    )
    (net (code "2") (name "/USBS1_D_P") (class "Default")
      (node (ref "U10") (pin "36") (pinfunction "USB_DP_36") (pintype "bidirectional"))
      (node (ref "U7") (pin "41") (pinfunction "USB_DP_DN1_41") (pintype "bidirectional"))
    )
    (net (code "3") (name "/USBS1_RX_N") (class "Default")
      (node (ref "C37") (pin "2") (pinfunction "2_2") (pintype "passive"))
      (node (ref "U10") (pin "42") (pinfunction "USB_SSTXM_42") (pintype "output"))
    )
    (net (code "4") (name "/USBS1_RX_P") (class "Default")
      (node (ref "C32") (pin "2") (pinfunction "2_2") (pintype "passive"))
      (node (ref "U10") (pin "43") (pinfunction "USB_SSTXP_43") (pintype "output"))
    )
    (net (code "5") (name "/USBS1_TX_N") (class "Default")
      (node (ref "C63") (pin "1") (pinfunction "1_1") (pintype "passive"))
      (node (ref "U10") (pin "45") (pinfunction "USB_SSRXM_45") (pintype "input"))
    )
    (net (code "6") (name "/USBS1_TX_P") (class "Default")
      (node (ref "C52") (pin "1") (pinfunction "1_1") (pintype "passive"))
      (node (ref "U10") (pin "46") (pinfunction "USB_SSRXP_46") (pintype "input"))
    )
    (net (code "7") (name "/USBS2_D_N") (class "Default")
      (node (ref "U15") (pin "35") (pinfunction "USB_DM_35") (pintype "bidirectional"))
      (node (ref "U7") (pin "15") (pinfunction "USB_DM_DN2_15") (pintype "bidirectional"))
    )
    (net (code "8") (name "/USBS2_D_P") (class "Default")
      (node (ref "U15") (pin "36") (pinfunction "USB_DP_36") (pintype "bidirectional"))
      (node (ref "U7") (pin "14") (pinfunction "USB_DP_DN2_14") (pintype "bidirectional"))
    )
    (net (code "9") (name "/USBS2_RX_N") (class "Default")
      (node (ref "C47") (pin "2") (pinfunction "2_2") (pintype "passive"))
      (node (ref "U15") (pin "42") (pinfunction "USB_SSTXM_42") (pintype "output"))
    )
    (net (code "10") (name "/USBS2_RX_P") (class "Default")
      (node (ref "C44") (pin "2") (pinfunction "2_2") (pintype "passive"))
      (node (ref "U15") (pin "43") (pinfunction "USB_SSTXP_43") (pintype "output"))
    )
    (net (code "11") (name "/USBS2_TX_N") (class "Default")
      (node (ref "C65") (pin "1") (pinfunction "1_1") (pintype "passive"))
      (node (ref "U15") (pin "45") (pinfunction "USB_SSRXM_45") (pintype "input"))
    )
    (net (code "12") (name "/USBS2_TX_P") (class "Default")
      (node (ref "C64") (pin "1") (pinfunction "1_1") (pintype "passive"))
      (node (ref "U15") (pin "46") (pinfunction "USB_SSRXP_46") (pintype "input"))
    )
    (net (code "13") (name "1.2VDC_A") (class "Default")
      (node (ref "C12") (pin "2") (pinfunction "2_2") (pintype "passive"))
      (node (ref "C125") (pin "1") (pinfunction "1_1") (pintype "passive"))
      (node (ref "C126") (pin "1") (pinfunction "1_1") (pintype "passive"))
      (node (ref "C14") (pin "2") (pinfunction "2_2") (pintype "passive"))
      (node (ref "C16") (pin "2") (pinfunction "2_2") (pintype "passive"))
      (node (ref "C18") (pin "2") (pinfunction "2_2") (pintype "passive"))
      (node (ref "C21") (pin "2") (pinfunction "2_2") (pintype "passive"))
      (node (ref "C23") (pin "2") (pinfunction "2_2") (pintype "passive"))
      (node (ref "L13") (pin "2") (pinfunction "2_2") (pintype "passive"))
      (node (ref "R44") (pin "1") (pinfunction "1_1") (pintype "passive"))
      (node (ref "U7") (pin "1") (pinfunction "VDD_1") (pintype "power_in"))
      (node (ref "U7") (pin "12") (pinfunction "VDD_12") (pintype "power_in"))
      (node (ref "U7") (pin "18") (pinfunction "VDD_18") (pintype "power_in"))
      (node (ref "U7") (pin "30") (pinfunction "VDD_30") (pintype "power_in"))
      (node (ref "U7") (pin "34") (pinfunction "VDD_34") (pintype "power_in"))
      (node (ref "U7") (pin "45") (pinfunction "VDD_45") (pintype "power_in"))
    )
    (net (code "14") (name "1.2VDC_B") (class "Default")
      (node (ref "C106") (pin "2") (pinfunction "2_2") (pintype "passive"))
      (node (ref "C107") (pin "2") (pinfunction "2_2") (pintype "passive"))
      (node (ref "C108") (pin "2") (pinfunction "2_2") (pintype "passive"))
      (node (ref "C109") (pin "2") (pinfunction "2_2") (pintype "passive"))
      (node (ref "C110") (pin "2") (pinfunction "2_2") (pintype "passive"))
      (node (ref "C111") (pin "2") (pinfunction "2_2") (pintype "passive"))
      (node (ref "C113") (pin "2") (pinfunction "2_2") (pintype "passive"))
      (node (ref "C115") (pin "2") (pinfunction "2_2") (pintype "passive"))
      (node (ref "C118") (pin "2") (pinfunction "2_2") (pintype "passive"))
      (node (ref "C120") (pin "2") (pinfunction "2_2") (pintype "passive"))
      (node (ref "C121") (pin "2") (pinfunction "2_2") (pintype "passive"))
      (node (ref "C13") (pin "2") (pinfunction "2_2") (pintype "passive"))
      (node (ref "C136") (pin "1") (pinfunction "1_1") (pintype "passive"))
      (node (ref "C137") (pin "1") (pinfunction "1_1") (pintype "passive"))
      (node (ref "C15") (pin "2") (pinfunction "2_2") (pintype "passive"))
      (node (ref "C17") (pin "2") (pinfunction "2_2") (pintype "passive"))
      (node (ref "C19") (pin "2") (pinfunction "2_2") (pintype "passive"))
      (node (ref "C22") (pin "2") (pinfunction "2_2") (pintype "passive"))
      (node (ref "C24") (pin "2") (pinfunction "2_2") (pintype "passive"))
      (node (ref "C27") (pin "2") (pinfunction "2_2") (pintype "passive"))
      (node (ref "C29") (pin "2") (pinfunction "2_2") (pintype "passive"))
      (node (ref "C31") (pin "2") (pinfunction "2_2") (pintype "passive"))
      (node (ref "C34") (pin "2") (pinfunction "2_2") (pintype "passive"))
      (node (ref "C36") (pin "2") (pinfunction "2_2") (pintype "passive"))
      (node (ref "L14") (pin "2") (pinfunction "2_2") (pintype "passive"))
      (node (ref "R49") (pin "1") (pinfunction "1_1") (pintype "passive"))
      (node (ref "U10") (pin "1") (pinfunction "VDD_1") (pintype "power_in"))
      (node (ref "U10") (pin "12") (pinfunction "VDD_12") (pintype "power_in"))
      (node (ref "U10") (pin "19") (pinfunction "VDD_19") (pintype "power_in"))
      (node (ref "U10") (pin "32") (pinfunction "VDD_32") (pintype "power_in"))
      (node (ref "U10") (pin "33") (pinfunction "VDD_33") (pintype "power_in"))
      (node (ref "U10") (pin "41") (pinfunction "VDD_41") (pintype "power_in"))
      (node (ref "U10") (pin "47") (pinfunction "VDD_47") (pintype "power_in"))
      (node (ref "U10") (pin "49") (pinfunction "VDD_49") (pintype "power_in"))
      (node (ref "U10") (pin "55") (pinfunction "VDD_55") (pintype "power_in"))
      (node (ref "U10") (pin "61") (pinfunction "VDD_61") (pintype "power_in"))
      (node (ref "U10") (pin "63") (pinfunction "VDD_63") (pintype "power_in"))
      (node (ref "U15") (pin "1") (pinfunction "VDD_1") (pintype "power_in"))
      (node (ref "U15") (pin "12") (pinfunction "VDD_12") (pintype "power_in"))
      (node (ref "U15") (pin "19") (pinfunction "VDD_19") (pintype "power_in"))
      (node (ref "U15") (pin "32") (pinfunction "VDD_32") (pintype "power_in"))
      (node (ref "U15") (pin "33") (pinfunction "VDD_33") (pintype "power_in"))
      (node (ref "U15") (pin "41") (pinfunction "VDD_41") (pintype "power_in"))
      (node (ref "U15") (pin "47") (pinfunction "VDD_47") (pintype "power_in"))
      (node (ref "U15") (pin "49") (pinfunction "VDD_49") (pintype "power_in"))
      (node (ref "U15") (pin "55") (pinfunction "VDD_55") (pintype "power_in"))
      (node (ref "U15") (pin "61") (pinfunction "VDD_61") (pintype "power_in"))
      (node (ref "U15") (pin "63") (pinfunction "VDD_63") (pintype "power_in"))
    )
    (net (code "15") (name "3v3_PER") (class "Default")
      (node (ref "C122") (pin "2") (pinfunction "2_2") (pintype "passive"))
      (node (ref "C127") (pin "2") (pinfunction "2_2") (pintype "passive"))
      (node (ref "C128") (pin "2") (pinfunction "2_2") (pintype "passive"))
      (node (ref "C129") (pin "2") (pinfunction "2_2") (pintype "passive"))
      (node (ref "C130") (pin "2") (pinfunction "2_2") (pintype "passive"))
      (node (ref "C131") (pin "2") (pinfunction "2_2") (pintype "passive"))
      (node (ref "C132") (pin "2") (pinfunction "2_2") (pintype "passive"))
      (node (ref "C26") (pin "2") (pinfunction "2_2") (pintype "passive"))
      (node (ref "C28") (pin "2") (pinfunction "2_2") (pintype "passive"))
      (node (ref "C30") (pin "2") (pinfunction "2_2") (pintype "passive"))
      (node (ref "C33") (pin "2") (pinfunction "2_2") (pintype "passive"))
      (node (ref "C35") (pin "2") (pinfunction "2_2") (pintype "passive"))
      (node (ref "C38") (pin "2") (pinfunction "2_2") (pintype "passive"))
      (node (ref "C39") (pin "2") (pinfunction "2_2") (pintype "passive"))
      (node (ref "C40") (pin "2") (pinfunction "2_2") (pintype "passive"))
      (node (ref "C41") (pin "2") (pinfunction "2_2") (pintype "passive"))
      (node (ref "C42") (pin "2") (pinfunction "2_2") (pintype "passive"))
      (node (ref "C43") (pin "2") (pinfunction "2_2") (pintype "passive"))
      (node (ref "C45") (pin "2") (pinfunction "2_2") (pintype "passive"))
      (node (ref "C46") (pin "2") (pinfunction "2_2") (pintype "passive"))
      (node (ref "C49") (pin "2") (pinfunction "2_2") (pintype "passive"))
      (node (ref "C51") (pin "2") (pinfunction "2_2") (pintype "passive"))
      (node (ref "R35") (pin "1") (pinfunction "1_1") (pintype "passive"))
      (node (ref "R36") (pin "1") (pinfunction "1_1") (pintype "passive"))
      (node (ref "R40") (pin "2") (pinfunction "2_2") (pintype "passive"))
      (node (ref "R41") (pin "2") (pinfunction "2_2") (pintype "passive"))
      (node (ref "R42") (pin "1") (pinfunction "1_1") (pintype "passive"))
      (node (ref "R43") (pin "1") (pinfunction "1_1") (pintype "passive"))
      (node (ref "R51") (pin "2") (pinfunction "2_2") (pintype "passive"))
      (node (ref "R52") (pin "2") (pinfunction "2_2") (pintype "passive"))
      (node (ref "R57") (pin "1") (pinfunction "1_1") (pintype "passive"))
      (node (ref "R62") (pin "1") (pinfunction "1_1") (pintype "passive"))
      (node (ref "U10") (pin "24") (pinfunction "VDD33_24") (pintype "power_in"))
      (node (ref "U10") (pin "34") (pinfunction "VDDA33_34") (pintype "power_in"))
      (node (ref "U10") (pin "40") (pinfunction "VDDA33_40") (pintype "power_in"))
      (node (ref "U10") (pin "48") (pinfunction "VDDA33_48") (pintype "power_in"))
      (node (ref "U10") (pin "51") (pinfunction "VDD33_51") (pintype "power_in"))
      (node (ref "U10") (pin "62") (pinfunction "VDDA33_62") (pintype "power_in"))
      (node (ref "U10") (pin "7") (pinfunction "VDD33_7") (pintype "power_in"))
      (node (ref "U15") (pin "24") (pinfunction "VDD33_24") (pintype "power_in"))
      (node (ref "U15") (pin "34") (pinfunction "VDDA33_34") (pintype "power_in"))
      (node (ref "U15") (pin "40") (pinfunction "VDDA33_40") (pintype "power_in"))
      (node (ref "U15") (pin "48") (pinfunction "VDDA33_48") (pintype "power_in"))
      (node (ref "U15") (pin "51") (pinfunction "VDD33_51") (pintype "power_in"))
      (node (ref "U15") (pin "62") (pinfunction "VDDA33_62") (pintype "power_in"))
      (node (ref "U15") (pin "7") (pinfunction "VDD33_7") (pintype "power_in"))
      (node (ref "U7") (pin "13") (pinfunction "VDD33_13") (pintype "power_in"))
      (node (ref "U7") (pin "23") (pinfunction "VDD33_23") (pintype "power_in"))
      (node (ref "U7") (pin "25") (pinfunction "VDD33_25") (pintype "power_in"))
      (node (ref "U7") (pin "33") (pinfunction "VDD33_33") (pintype "power_in"))
      (node (ref "U7") (pin "37") (pinfunction "VDD33_37") (pintype "power_in"))
      (node (ref "U7") (pin "40") (pinfunction "VDD33_40") (pintype "power_in"))
      (node (ref "U7") (pin "48") (pinfunction "VDD33_48") (pintype "power_in"))
      (node (ref "U7") (pin "7") (pinfunction "VDD33_7") (pintype "power_in"))
    )
    (net (code "16") (name "5v_PER") (class "Default")
      (node (ref "C10") (pin "1") (pinfunction "1_1") (pintype "passive"))
      (node (ref "C123") (pin "1") (pinfunction "1_1") (pintype "passive"))
      (node (ref "C124") (pin "1") (pinfunction "1_1") (pintype "passive"))
      (node (ref "C134") (pin "1") (pinfunction "1_1") (pintype "passive"))
      (node (ref "C135") (pin "1") (pinfunction "1_1") (pintype "passive"))
      (node (ref "C78") (pin "1") (pinfunction "1_1") (pintype "passive"))
      (node (ref "C86") (pin "1") (pinfunction "1_1") (pintype "passive"))
      (node (ref "C88") (pin "1") (pinfunction "1_1") (pintype "passive"))
      (node (ref "FB5") (pin "1") (pinfunction "1_1") (pintype "passive"))
      (node (ref "FB7") (pin "1") (pinfunction "1_1") (pintype "passive"))
      (node (ref "R13") (pin "1") (pinfunction "1_1") (pintype "passive"))
      (node (ref "R37") (pin "1") (pinfunction "1_1") (pintype "passive"))
      (node (ref "R46") (pin "1") (pinfunction "1_1") (pintype "passive"))
      (node (ref "U16") (pin "2") (pinfunction "EN_2") (pintype "passive"))
      (node (ref "U16") (pin "3") (pinfunction "VIN_3") (pintype "passive"))
      (node (ref "U17") (pin "2") (pinfunction "EN_2") (pintype "passive"))
      (node (ref "U17") (pin "3") (pinfunction "VIN_3") (pintype "passive"))
    )
    (net (code "17") (name "12v_PER") (class "Default")
      (node (ref "C6") (pin "1") (pinfunction "1_1") (pintype "passive"))
      (node (ref "C7") (pin "1") (pinfunction "1_1") (pintype "passive"))
      (node (ref "C8") (pin "1") (pinfunction "1_1") (pintype "passive"))
      (node (ref "C9") (pin "1") (pinfunction "1_1") (pintype "passive"))
      (node (ref "FB6") (pin "1") (pinfunction "1_1") (pintype "passive"))
      (node (ref "FB8") (pin "1") (pinfunction "1_1") (pintype "passive"))
    )
    (net (code "18") (name "GND") (class "Default")
      (node (ref "C10") (pin "2") (pinfunction "2_2") (pintype "passive"))
      (node (ref "C106") (pin "1") (pinfunction "1_1") (pintype "passive"))
      (node (ref "C107") (pin "1") (pinfunction "1_1") (pintype "passive"))
      (node (ref "C108") (pin "1") (pinfunction "1_1") (pintype "passive"))
      (node (ref "C109") (pin "1") (pinfunction "1_1") (pintype "passive"))
      (node (ref "C11") (pin "1") (pinfunction "1_1") (pintype "passive"))
      (node (ref "C110") (pin "1") (pinfunction "1_1") (pintype "passive"))
      (node (ref "C111") (pin "1") (pinfunction "1_1") (pintype "passive"))
      (node (ref "C113") (pin "1") (pinfunction "1_1") (pintype "passive"))
      (node (ref "C115") (pin "1") (pinfunction "1_1") (pintype "passive"))
      (node (ref "C118") (pin "1") (pinfunction "1_1") (pintype "passive"))
      (node (ref "C12") (pin "1") (pinfunction "1_1") (pintype "passive"))
      (node (ref "C120") (pin "1") (pinfunction "1_1") (pintype "passive"))
      (node (ref "C121") (pin "1") (pinfunction "1_1") (pintype "passive"))
      (node (ref "C122") (pin "1") (pinfunction "1_1") (pintype "passive"))
      (node (ref "C123") (pin "2") (pinfunction "2_2") (pintype "passive"))
      (node (ref "C124") (pin "2") (pinfunction "2_2") (pintype "passive"))
      (node (ref "C125") (pin "2") (pinfunction "2_2") (pintype "passive"))
      (node (ref "C126") (pin "2") (pinfunction "2_2") (pintype "passive"))
      (node (ref "C127") (pin "1") (pinfunction "1_1") (pintype "passive"))
      (node (ref "C128") (pin "1") (pinfunction "1_1") (pintype "passive"))
      (node (ref "C129") (pin "1") (pinfunction "1_1") (pintype "passive"))
      (node (ref "C13") (pin "1") (pinfunction "1_1") (pintype "passive"))
      (node (ref "C130") (pin "1") (pinfunction "1_1") (pintype "passive"))
      (node (ref "C131") (pin "1") (pinfunction "1_1") (pintype "passive"))
      (node (ref "C132") (pin "1") (pinfunction "1_1") (pintype "passive"))
      (node (ref "C134") (pin "2") (pinfunction "2_2") (pintype "passive"))
      (node (ref "C135") (pin "2") (pinfunction "2_2") (pintype "passive"))
      (node (ref "C136") (pin "2") (pinfunction "2_2") (pintype "passive"))
      (node (ref "C137") (pin "2") (pinfunction "2_2") (pintype "passive"))
      (node (ref "C14") (pin "1") (pinfunction "1_1") (pintype "passive"))
      (node (ref "C15") (pin "1") (pinfunction "1_1") (pintype "passive"))
      (node (ref "C16") (pin "1") (pinfunction "1_1") (pintype "passive"))
      (node (ref "C17") (pin "1") (pinfunction "1_1") (pintype "passive"))
      (node (ref "C18") (pin "1") (pinfunction "1_1") (pintype "passive"))
      (node (ref "C19") (pin "1") (pinfunction "1_1") (pintype "passive"))
      (node (ref "C21") (pin "1") (pinfunction "1_1") (pintype "passive"))
      (node (ref "C22") (pin "1") (pinfunction "1_1") (pintype "passive"))
      (node (ref "C23") (pin "1") (pinfunction "1_1") (pintype "passive"))
      (node (ref "C24") (pin "1") (pinfunction "1_1") (pintype "passive"))
      (node (ref "C26") (pin "1") (pinfunction "1_1") (pintype "passive"))
      (node (ref "C27") (pin "1") (pinfunction "1_1") (pintype "passive"))
      (node (ref "C28") (pin "1") (pinfunction "1_1") (pintype "passive"))
      (node (ref "C29") (pin "1") (pinfunction "1_1") (pintype "passive"))
      (node (ref "C30") (pin "1") (pinfunction "1_1") (pintype "passive"))
      (node (ref "C31") (pin "1") (pinfunction "1_1") (pintype "passive"))
      (node (ref "C33") (pin "1") (pinfunction "1_1") (pintype "passive"))
      (node (ref "C34") (pin "1") (pinfunction "1_1") (pintype "passive"))
      (node (ref "C35") (pin "1") (pinfunction "1_1") (pintype "passive"))
      (node (ref "C36") (pin "1") (pinfunction "1_1") (pintype "passive"))
      (node (ref "C38") (pin "1") (pinfunction "1_1") (pintype "passive"))
      (node (ref "C39") (pin "1") (pinfunction "1_1") (pintype "passive"))
      (node (ref "C40") (pin "1") (pinfunction "1_1") (pintype "passive"))
      (node (ref "C41") (pin "1") (pinfunction "1_1") (pintype "passive"))
      (node (ref "C42") (pin "1") (pinfunction "1_1") (pintype "passive"))
      (node (ref "C43") (pin "1") (pinfunction "1_1") (pintype "passive"))
      (node (ref "C45") (pin "1") (pinfunction "1_1") (pintype "passive"))
      (node (ref "C46") (pin "1") (pinfunction "1_1") (pintype "passive"))
      (node (ref "C49") (pin "1") (pinfunction "1_1") (pintype "passive"))
      (node (ref "C51") (pin "1") (pinfunction "1_1") (pintype "passive"))
      (node (ref "C6") (pin "2") (pinfunction "2_2") (pintype "passive"))
      (node (ref "C66") (pin "1") (pinfunction "1_1") (pintype "passive"))
      (node (ref "C67") (pin "1") (pinfunction "1_1") (pintype "passive"))
      (node (ref "C7") (pin "2") (pinfunction "2_2") (pintype "passive"))
      (node (ref "C78") (pin "2") (pinfunction "2_2") (pintype "passive"))
      (node (ref "C8") (pin "2") (pinfunction "2_2") (pintype "passive"))
      (node (ref "C86") (pin "2") (pinfunction "2_2") (pintype "passive"))
      (node (ref "C88") (pin "2") (pinfunction "2_2") (pintype "passive"))
      (node (ref "C9") (pin "2") (pinfunction "2_2") (pintype "passive"))
      (node (ref "M1") (pin "2") (pinfunction "2_2") (pintype "passive"))
      (node (ref "M1") (pin "3") (pinfunction "3_3") (pintype "passive"))
      (node (ref "M2") (pin "2") (pinfunction "2_2") (pintype "passive"))
      (node (ref "M2") (pin "3") (pinfunction "3_3") (pintype "passive"))
      (node (ref "R11") (pin "1") (pinfunction "1_1") (pintype "passive"))
      (node (ref "R12") (pin "1") (pinfunction "1_1") (pintype "passive"))
      (node (ref "R14") (pin "1") (pinfunction "1_1") (pintype "passive"))
      (node (ref "R15") (pin "1") (pinfunction "1_1") (pintype "passive"))
      (node (ref "R16") (pin "1") (pinfunction "1_1") (pintype "passive"))
      (node (ref "R38") (pin "1") (pinfunction "1_1") (pintype "passive"))
      (node (ref "R45") (pin "1") (pinfunction "1_1") (pintype "passive"))
      (node (ref "R47") (pin "1") (pinfunction "1_1") (pintype "passive"))
      (node (ref "R50") (pin "1") (pinfunction "1_1") (pintype "passive"))
      (node (ref "S1") (pin "1") (pinfunction "1_1") (pintype "passive"))
      (node (ref "S1") (pin "4") (pinfunction "4_4") (pintype "passive"))
      (node (ref "S1") (pin "7") (pinfunction "7_7") (pintype "passive"))
      (node (ref "S2") (pin "1") (pinfunction "1_1") (pintype "passive"))
      (node (ref "S2") (pin "4") (pinfunction "4_4") (pintype "passive"))
      (node (ref "S2") (pin "7") (pinfunction "7_7") (pintype "passive"))
      (node (ref "U10") (pin "44") (pinfunction "VSS_44") (pintype "power_in"))
      (node (ref "U10") (pin "58") (pinfunction "VSS_58") (pintype "power_in"))
      (node (ref "U10") (pin "65") (pinfunction "EXP_VSS_65") (pintype "power_in"))
      (node (ref "U15") (pin "44") (pinfunction "VSS_44") (pintype "power_in"))
      (node (ref "U15") (pin "58") (pinfunction "VSS_58") (pintype "power_in"))
      (node (ref "U15") (pin "65") (pinfunction "EXP_VSS_65") (pintype "power_in"))
      (node (ref "U16") (pin "4") (pinfunction "GND_4") (pintype "power_in"))
      (node (ref "U17") (pin "4") (pinfunction "GND_4") (pintype "power_in"))
      (node (ref "U7") (pin "49") (pinfunction "GND_49") (pintype "power_in"))
      (node (ref "Y2") (pin "2") (pinfunction "GND_2") (pintype "power_in"))
      (node (ref "Y2") (pin "4") (pinfunction "GND_4") (pintype "power_in"))
      (node (ref "Y4") (pin "2") (pinfunction "GND_2") (pintype "power_in"))
      (node (ref "Y4") (pin "4") (pinfunction "GND_4") (pintype "power_in"))
      (node (ref "Y5") (pin "2") (pinfunction "GND_2") (pintype "power_in"))
      (node (ref "Y5") (pin "4") (pinfunction "GND_4") (pintype "power_in"))
    )
    (net (code "19") (name "Net-(FB5-Pad2)") (class "Default")
      (node (ref "FB5") (pin "2") (pinfunction "2_2") (pintype "passive"))
      (node (ref "M1") (pin "1") (pinfunction "1_1") (pintype "passive"))
    )
    (net (code "20") (name "Net-(FB6-Pad2)") (class "Default")
      (node (ref "FB6") (pin "2") (pinfunction "2_2") (pintype "passive"))
      (node (ref "M1") (pin "4") (pinfunction "4_4") (pintype "passive"))
    )
    (net (code "21") (name "Net-(FB7-Pad2)") (class "Default")
      (node (ref "FB7") (pin "2") (pinfunction "2_2") (pintype "passive"))
      (node (ref "M2") (pin "1") (pinfunction "1_1") (pintype "passive"))
    )
    (net (code "22") (name "Net-(FB8-Pad2)") (class "Default")
      (node (ref "FB8") (pin "2") (pinfunction "2_2") (pintype "passive"))
      (node (ref "M2") (pin "4") (pinfunction "4_4") (pintype "passive"))
    )
    (net (code "23") (name "Net-(LED2-Anode)") (class "Default")
      (node (ref "LED2") (pin "2") (pinfunction "Anode_2") (pintype "passive"))
      (node (ref "R40") (pin "1") (pinfunction "1_1") (pintype "passive"))
    )
    (net (code "24") (name "Net-(LED2-Cathode)") (class "Default")
      (node (ref "LED2") (pin "1") (pinfunction "Cathode_1") (pintype "passive"))
      (node (ref "U10") (pin "2") (pinfunction "PWM0_2") (pintype "output"))
    )
    (net (code "25") (name "Net-(LED3-Anode)") (class "Default")
      (node (ref "LED3") (pin "2") (pinfunction "Anode_2") (pintype "passive"))
      (node (ref "R41") (pin "1") (pinfunction "1_1") (pintype "passive"))
    )
    (net (code "26") (name "Net-(LED3-Cathode)") (class "Default")
      (node (ref "LED3") (pin "1") (pinfunction "Cathode_1") (pintype "passive"))
      (node (ref "U10") (pin "3") (pinfunction "PWM1_3") (pintype "output"))
    )
    (net (code "27") (name "Net-(LED4-Anode)") (class "Default")
      (node (ref "LED4") (pin "2") (pinfunction "Anode_2") (pintype "passive"))
      (node (ref "R51") (pin "1") (pinfunction "1_1") (pintype "passive"))
    )
    (net (code "28") (name "Net-(LED4-Cathode)") (class "Default")
      (node (ref "LED4") (pin "1") (pinfunction "Cathode_1") (pintype "passive"))
      (node (ref "U15") (pin "2") (pinfunction "PWM0_2") (pintype "output"))
    )
    (net (code "29") (name "Net-(LED5-Anode)") (class "Default")
      (node (ref "LED5") (pin "2") (pinfunction "Anode_2") (pintype "passive"))
      (node (ref "R52") (pin "1") (pinfunction "1_1") (pintype "passive"))
    )
    (net (code "30") (name "Net-(LED5-Cathode)") (class "Default")
      (node (ref "LED5") (pin "1") (pinfunction "Cathode_1") (pintype "passive"))
      (node (ref "U15") (pin "3") (pinfunction "PWM1_3") (pintype "output"))
    )
    (net (code "31") (name "Net-(U7-GANGED{slash}SMBA2{slash}HS_UP)") (class "Default")
      (node (ref "R15") (pin "2") (pinfunction "2_2") (pintype "passive"))
      (node (ref "U7") (pin "35") (pinfunction "GANGED/SMBA2/HS_UP_35") (pintype "input"))
    )
    (net (code "32") (name "Net-(U7-GRSTZ)") (class "Default")
      (node (ref "C11") (pin "2") (pinfunction "2_2") (pintype "passive"))
      (node (ref "U7") (pin "11") (pinfunction "GRSTZ_11") (pintype "input"))
    )
    (net (code "33") (name "Net-(U7-PWRCRL_POL{slash}SS_DN1)") (class "Default")
      (node (ref "R14") (pin "2") (pinfunction "2_2") (pintype "passive"))
      (node (ref "U7") (pin "21") (pinfunction "PWRCRL_POL/SS_DN1_21") (pintype "bidirectional"))
    )
    (net (code "34") (name "Net-(U7-TEST)") (class "Default")
      (node (ref "R16") (pin "2") (pinfunction "2_2") (pintype "passive"))
      (node (ref "U7") (pin "10") (pinfunction "TEST_10") (pintype "input"))
    )
    (net (code "35") (name "Net-(U7-USB_R1)") (class "Default")
      (node (ref "R11") (pin "2") (pinfunction "2_2") (pintype "passive"))
      (node (ref "U7") (pin "24") (pinfunction "USB_R1_24") (pintype "input"))
    )
    (net (code "36") (name "Net-(U7-USB_SSRXM_DN1)") (class "Default")
      (node (ref "C37") (pin "1") (pinfunction "1_1") (pintype "passive"))
      (node (ref "U7") (pin "47") (pinfunction "USB_SSRXM_DN1_47") (pintype "input"))
    )
    (net (code "37") (name "Net-(U7-USB_SSRXM_DN2)") (class "Default")
      (node (ref "C47") (pin "1") (pinfunction "1_1") (pintype "passive"))
      (node (ref "U7") (pin "20") (pinfunction "USB_SSRXM_DN2_20") (pintype "input"))
    )
    (net (code "38") (name "Net-(U7-USB_SSRXP_DN1)") (class "Default")
      (node (ref "C32") (pin "1") (pinfunction "1_1") (pintype "passive"))
      (node (ref "U7") (pin "46") (pinfunction "USB_SSRXP_DN1_46") (pintype "input"))
    )
    (net (code "39") (name "Net-(U7-USB_SSRXP_DN2)") (class "Default")
      (node (ref "C44") (pin "1") (pinfunction "1_1") (pintype "passive"))
      (node (ref "U7") (pin "19") (pinfunction "USB_SSRXP_DN2_19") (pintype "input"))
    )
    (net (code "40") (name "Net-(U7-USB_SSTXM_DN1)") (class "Default")
      (node (ref "C63") (pin "2") (pinfunction "2_2") (pintype "passive"))
      (node (ref "U7") (pin "44") (pinfunction "USB_SSTXM_DN1_44") (pintype "output"))
    )
    (net (code "41") (name "Net-(U7-USB_SSTXM_DN2)") (class "Default")
      (node (ref "C65") (pin "2") (pinfunction "2_2") (pintype "passive"))
      (node (ref "U7") (pin "17") (pinfunction "USB_SSTXM_DN2_17") (pintype "output"))
    )
    (net (code "42") (name "Net-(U7-USB_SSTXM_UP)") (class "Default")
      (node (ref "C50") (pin "2") (pinfunction "2_2") (pintype "passive"))
      (node (ref "U7") (pin "28") (pinfunction "USB_SSTXM_UP_28") (pintype "output"))
    )
    (net (code "43") (name "Net-(U7-USB_SSTXP_DN1)") (class "Default")
      (node (ref "C52") (pin "2") (pinfunction "2_2") (pintype "passive"))
      (node (ref "U7") (pin "43") (pinfunction "USB_SSTXP_DN1_43") (pintype "output"))
    )
    (net (code "44") (name "Net-(U7-USB_SSTXP_DN2)") (class "Default")
      (node (ref "C64") (pin "2") (pinfunction "2_2") (pintype "passive"))
      (node (ref "U7") (pin "16") (pinfunction "USB_SSTXP_DN2_16") (pintype "output"))
    )
    (net (code "45") (name "Net-(U7-USB_SSTXP_UP)") (class "Default")
      (node (ref "C48") (pin "2") (pinfunction "2_2") (pintype "passive"))
      (node (ref "U7") (pin "29") (pinfunction "USB_SSTXP_UP_29") (pintype "output"))
    )
    (net (code "46") (name "Net-(U7-USB_VBUS)") (class "Default")
      (node (ref "R12") (pin "2") (pinfunction "2_2") (pintype "passive"))
      (node (ref "R13") (pin "2") (pinfunction "2_2") (pintype "passive"))
      (node (ref "U7") (pin "9") (pinfunction "USB_VBUS_9") (pintype "input"))
    )
    (net (code "47") (name "Net-(U7-XI)") (class "Default")
      (node (ref "C66") (pin "2") (pinfunction "2_2") (pintype "passive"))
      (node (ref "R17") (pin "1") (pinfunction "1_1") (pintype "passive"))
      (node (ref "U7") (pin "38") (pinfunction "XI_38") (pintype "input"))
      (node (ref "Y2") (pin "3") (pintype "passive"))
    )
    (net (code "48") (name "Net-(U7-XO)") (class "Default")
      (node (ref "C67") (pin "2") (pinfunction "2_2") (pintype "passive"))
      (node (ref "R17") (pin "2") (pinfunction "2_2") (pintype "passive"))
      (node (ref "U7") (pin "39") (pinfunction "XO_39") (pintype "output"))
      (node (ref "Y2") (pin "1") (pintype "passive"))
    )
    (net (code "49") (name "Net-(U10-FREQSEL0)") (class "Default")
      (node (ref "R35") (pin "2") (pinfunction "2_2") (pintype "passive"))
      (node (ref "U10") (pin "30") (pinfunction "FREQSEL0_30") (pintype "input"))
    )
    (net (code "50") (name "Net-(U10-FREQSEL1)") (class "Default")
      (node (ref "R36") (pin "2") (pinfunction "2_2") (pintype "passive"))
      (node (ref "U10") (pin "31") (pinfunction "FREQSEL1_31") (pintype "input"))
    )
    (net (code "51") (name "Net-(U10-GRSTZ)") (class "Default")
      (node (ref "R57") (pin "2") (pinfunction "2_2") (pintype "passive"))
      (node (ref "U10") (pin "4") (pinfunction "GRSTZ_4") (pintype "input"))
    )
    (net (code "52") (name "Net-(U10-SATA_RXM)") (class "Default")
      (node (ref "C104") (pin "1") (pinfunction "1_1") (pintype "passive"))
      (node (ref "U10") (pin "59") (pinfunction "SATA_RXM_59") (pintype "input"))
    )
    (net (code "53") (name "Net-(U10-SATA_RXP)") (class "Default")
      (node (ref "C102") (pin "1") (pinfunction "1_1") (pintype "passive"))
      (node (ref "U10") (pin "60") (pinfunction "SATA_RXP_60") (pintype "input"))
    )
    (net (code "54") (name "Net-(U10-SATA_TXM)") (class "Default")
      (node (ref "C105") (pin "1") (pinfunction "1_1") (pintype "passive"))
      (node (ref "U10") (pin "56") (pinfunction "SATA_TXM_56") (pintype "output"))
    )
    (net (code "55") (name "Net-(U10-SATA_TXP)") (class "Default")
      (node (ref "C103") (pin "1") (pinfunction "1_1") (pintype "passive"))
      (node (ref "U10") (pin "57") (pinfunction "SATA_TXP_57") (pintype "output"))
    )
    (net (code "56") (name "Net-(U10-USB_R1)") (class "Default")
      (node (ref "R39") (pin "2") (pinfunction "2_2") (pintype "passive"))
      (node (ref "U10") (pin "38") (pinfunction "USB_R1_38") (pintype "output"))
    )
    (net (code "57") (name "Net-(U10-USB_R1RTN)") (class "Default")
      (node (ref "R39") (pin "1") (pinfunction "1_1") (pintype "passive"))
      (node (ref "U10") (pin "39") (pinfunction "USB_R1RTN_39") (pintype "input"))
    )
    (net (code "58") (name "Net-(U10-USB_VBUS)") (class "Default")
      (node (ref "R37") (pin "2") (pinfunction "2_2") (pintype "passive"))
      (node (ref "R38") (pin "2") (pinfunction "2_2") (pintype "passive"))
      (node (ref "U10") (pin "50") (pinfunction "USB_VBUS_50") (pintype "input"))
    )
    (net (code "59") (name "Net-(U10-XI)") (class "Default")
      (node (ref "U10") (pin "52") (pinfunction "XI_52") (pintype "input"))
      (node (ref "Y4") (pin "3") (pintype "passive"))
    )
    (net (code "60") (name "Net-(U10-XO)") (class "Default")
      (node (ref "U10") (pin "54") (pinfunction "XO_54") (pintype "output"))
      (node (ref "Y4") (pin "1") (pintype "passive"))
    )
    (net (code "61") (name "Net-(U15-FREQSEL0)") (class "Default")
      (node (ref "R42") (pin "2") (pinfunction "2_2") (pintype "passive"))
      (node (ref "U15") (pin "30") (pinfunction "FREQSEL0_30") (pintype "input"))
    )
    (net (code "62") (name "Net-(U15-FREQSEL1)") (class "Default")
      (node (ref "R43") (pin "2") (pinfunction "2_2") (pintype "passive"))
      (node (ref "U15") (pin "31") (pinfunction "FREQSEL1_31") (pintype "input"))
    )
    (net (code "63") (name "Net-(U15-GRSTZ)") (class "Default")
      (node (ref "R62") (pin "2") (pinfunction "2_2") (pintype "passive"))
      (node (ref "U15") (pin "4") (pinfunction "GRSTZ_4") (pintype "input"))
    )
    (net (code "64") (name "Net-(U15-SATA_RXM)") (class "Default")
      (node (ref "C117") (pin "1") (pinfunction "1_1") (pintype "passive"))
      (node (ref "U15") (pin "59") (pinfunction "SATA_RXM_59") (pintype "input"))
    )
    (net (code "65") (name "Net-(U15-SATA_RXP)") (class "Default")
      (node (ref "C112") (pin "1") (pinfunction "1_1") (pintype "passive"))
      (node (ref "U15") (pin "60") (pinfunction "SATA_RXP_60") (pintype "input"))
    )
    (net (code "66") (name "Net-(U15-SATA_TXM)") (class "Default")
      (node (ref "C119") (pin "1") (pinfunction "1_1") (pintype "passive"))
      (node (ref "U15") (pin "56") (pinfunction "SATA_TXM_56") (pintype "output"))
    )
    (net (code "67") (name "Net-(U15-SATA_TXP)") (class "Default")
      (node (ref "C114") (pin "1") (pinfunction "1_1") (pintype "passive"))
      (node (ref "U15") (pin "57") (pinfunction "SATA_TXP_57") (pintype "output"))
    )
    (net (code "68") (name "Net-(U15-USB_R1)") (class "Default")
      (node (ref "R48") (pin "2") (pinfunction "2_2") (pintype "passive"))
      (node (ref "U15") (pin "38") (pinfunction "USB_R1_38") (pintype "output"))
    )
    (net (code "69") (name "Net-(U15-USB_R1RTN)") (class "Default")
      (node (ref "R48") (pin "1") (pinfunction "1_1") (pintype "passive"))
      (node (ref "U15") (pin "39") (pinfunction "USB_R1RTN_39") (pintype "input"))
    )
    (net (code "70") (name "Net-(U15-USB_VBUS)") (class "Default")
      (node (ref "R46") (pin "2") (pinfunction "2_2") (pintype "passive"))
      (node (ref "R47") (pin "2") (pinfunction "2_2") (pintype "passive"))
      (node (ref "U15") (pin "50") (pinfunction "USB_VBUS_50") (pintype "input"))
    )
    (net (code "71") (name "Net-(U15-XI)") (class "Default")
      (node (ref "U15") (pin "52") (pinfunction "XI_52") (pintype "input"))
      (node (ref "Y5") (pin "3") (pintype "passive"))
    )
    (net (code "72") (name "Net-(U15-XO)") (class "Default")
      (node (ref "U15") (pin "54") (pinfunction "XO_54") (pintype "output"))
      (node (ref "Y5") (pin "1") (pintype "passive"))
    )
    (net (code "73") (name "Net-(U16-BST)") (class "Default")
      (node (ref "C116") (pin "1") (pinfunction "1_1") (pintype "passive"))
      (node (ref "U16") (pin "6") (pinfunction "BST_6") (pintype "passive"))
    )
    (net (code "74") (name "Net-(U16-FB)") (class "Default")
      (node (ref "R44") (pin "2") (pinfunction "2_2") (pintype "passive"))
      (node (ref "R45") (pin "2") (pinfunction "2_2") (pintype "passive"))
      (node (ref "U16") (pin "1") (pinfunction "FB_1") (pintype "passive"))
    )
    (net (code "75") (name "Net-(U16-SW)") (class "Default")
      (node (ref "C116") (pin "2") (pinfunction "2_2") (pintype "passive"))
      (node (ref "L13") (pin "1") (pinfunction "1_1") (pintype "passive"))
      (node (ref "U16") (pin "5") (pinfunction "SW_5") (pintype "passive"))
    )
    (net (code "76") (name "Net-(U17-BST)") (class "Default")
      (node (ref "C133") (pin "1") (pinfunction "1_1") (pintype "passive"))
      (node (ref "U17") (pin "6") (pinfunction "BST_6") (pintype "passive"))
    )
    (net (code "77") (name "Net-(U17-FB)") (class "Default")
      (node (ref "R49") (pin "2") (pinfunction "2_2") (pintype "passive"))
      (node (ref "R50") (pin "2") (pinfunction "2_2") (pintype "passive"))
      (node (ref "U17") (pin "1") (pinfunction "FB_1") (pintype "passive"))
    )
    (net (code "78") (name "Net-(U17-SW)") (class "Default")
      (node (ref "C133") (pin "2") (pinfunction "2_2") (pintype "passive"))
      (node (ref "L14") (pin "1") (pinfunction "1_1") (pintype "passive"))
      (node (ref "U17") (pin "5") (pinfunction "SW_5") (pintype "passive"))
    )
    (net (code "79") (name "S1_RX_N") (class "Default")
      (node (ref "C104") (pin "2") (pinfunction "2_2") (pintype "passive"))
      (node (ref "S1") (pin "5") (pinfunction "5_5") (pintype "passive"))
    )
    (net (code "80") (name "S1_RX_P") (class "Default")
      (node (ref "C102") (pin "2") (pinfunction "2_2") (pintype "passive"))
      (node (ref "S1") (pin "6") (pinfunction "6_6") (pintype "passive"))
    )
    (net (code "81") (name "S1_TX_N") (class "Default")
      (node (ref "C105") (pin "2") (pinfunction "2_2") (pintype "passive"))
      (node (ref "S1") (pin "3") (pinfunction "3_3") (pintype "passive"))
    )
    (net (code "82") (name "S1_TX_P") (class "Default")
      (node (ref "C103") (pin "2") (pinfunction "2_2") (pintype "passive"))
      (node (ref "S1") (pin "2") (pinfunction "2_2") (pintype "passive"))
    )
    (net (code "83") (name "S2_RX_N") (class "Default")
      (node (ref "C117") (pin "2") (pinfunction "2_2") (pintype "passive"))
      (node (ref "S2") (pin "5") (pinfunction "5_5") (pintype "passive"))
    )
    (net (code "84") (name "S2_RX_P") (class "Default")
      (node (ref "C112") (pin "2") (pinfunction "2_2") (pintype "passive"))
      (node (ref "S2") (pin "6") (pinfunction "6_6") (pintype "passive"))
    )
    (net (code "85") (name "S2_TX_N") (class "Default")
      (node (ref "C119") (pin "2") (pinfunction "2_2") (pintype "passive"))
      (node (ref "S2") (pin "3") (pinfunction "3_3") (pintype "passive"))
    )
    (net (code "86") (name "S2_TX_P") (class "Default")
      (node (ref "C114") (pin "2") (pinfunction "2_2") (pintype "passive"))
      (node (ref "S2") (pin "2") (pinfunction "2_2") (pintype "passive"))
    )
    (net (code "87") (name "USB3-0-D_N") (class "Default")
      (node (ref "U7") (pin "27") (pinfunction "USB_DM_UP_27") (pintype "bidirectional"))
    )
    (net (code "88") (name "USB3-0-D_P") (class "Default")
      (node (ref "U7") (pin "26") (pinfunction "USB_DP_UP_26") (pintype "bidirectional"))
    )
    (net (code "89") (name "USB3-0-RX_N") (class "Default")
      (node (ref "C50") (pin "1") (pinfunction "1_1") (pintype "passive"))
    )
    (net (code "90") (name "USB3-0-RX_P") (class "Default")
      (node (ref "C48") (pin "1") (pinfunction "1_1") (pintype "passive"))
    )
    (net (code "91") (name "USB3-0-TX_N") (class "Default")
      (node (ref "U7") (pin "31") (pinfunction "USB_SSRXM_UP_31") (pintype "input"))
    )
    (net (code "92") (name "USB3-0-TX_P") (class "Default")
      (node (ref "U7") (pin "32") (pinfunction "USB_SSRXP_UP_32") (pintype "input"))
    )
    (net (code "93") (name "unconnected-(U7-FULLPWRMGMTZ{slash}SMBA1{slash}SS_UP-Pad36)") (class "Default")
      (node (ref "U7") (pin "36") (pinfunction "FULLPWRMGMTZ/SMBA1/SS_UP_36") (pintype "input"))
    )
    (net (code "94") (name "unconnected-(U7-OVERCUR1Z-Pad5)") (class "Default")
      (node (ref "U7") (pin "5") (pinfunction "OVERCUR1Z_5") (pintype "input"))
    )
    (net (code "95") (name "unconnected-(U7-OVERCUR2Z-Pad8)") (class "Default")
      (node (ref "U7") (pin "8") (pinfunction "OVERCUR2Z_8") (pintype "input"))
    )
    (net (code "96") (name "unconnected-(U7-PWRCTL1{slash}BATEN1-Pad4)") (class "Default")
      (node (ref "U7") (pin "4") (pinfunction "PWRCTL1/BATEN1_4") (pintype "bidirectional"))
    )
    (net (code "97") (name "unconnected-(U7-PWRCTL2{slash}BATEN2-Pad6)") (class "Default")
      (node (ref "U7") (pin "6") (pinfunction "PWRCTL2/BATEN2_6") (pintype "bidirectional"))
    )
    (net (code "98") (name "unconnected-(U7-SCL{slash}SMBCLK-Pad2)") (class "Default")
      (node (ref "U7") (pin "2") (pinfunction "SCL/SMBCLK_2") (pintype "bidirectional"))
    )
    (net (code "99") (name "unconnected-(U7-SDA{slash}SMBDAT-Pad3)") (class "Default")
      (node (ref "U7") (pin "3") (pinfunction "SDA/SMBDAT_3") (pintype "bidirectional"))
    )
    (net (code "100") (name "unconnected-(U7-SMBUSZ{slash}SS_DN2-Pad22)") (class "Default")
      (node (ref "U7") (pin "22") (pinfunction "SMBUSZ/SS_DN2_22") (pintype "input"))
    )
    (net (code "101") (name "unconnected-(U10-GPIO0-Pad8)") (class "Default")
      (node (ref "U10") (pin "8") (pinfunction "GPIO0_8") (pintype "bidirectional"))
    )
    (net (code "102") (name "unconnected-(U10-GPIO1-Pad9)") (class "Default")
      (node (ref "U10") (pin "9") (pinfunction "GPIO1_9") (pintype "bidirectional"))
    )
    (net (code "103") (name "unconnected-(U10-GPIO2-Pad10)") (class "Default")
      (node (ref "U10") (pin "10") (pinfunction "GPIO2_10") (pintype "bidirectional"))
    )
    (net (code "104") (name "unconnected-(U10-GPIO3-Pad11)") (class "Default")
      (node (ref "U10") (pin "11") (pinfunction "GPIO3_11") (pintype "bidirectional"))
    )
    (net (code "105") (name "unconnected-(U10-GPIO4-Pad13)") (class "Default")
      (node (ref "U10") (pin "13") (pinfunction "GPIO4_13") (pintype "bidirectional"))
    )
    (net (code "106") (name "unconnected-(U10-GPIO5-Pad14)") (class "Default")
      (node (ref "U10") (pin "14") (pinfunction "GPIO5_14") (pintype "bidirectional"))
    )
    (net (code "107") (name "unconnected-(U10-GPIO6-Pad15)") (class "Default")
      (node (ref "U10") (pin "15") (pinfunction "GPIO6_15") (pintype "bidirectional"))
    )
    (net (code "108") (name "unconnected-(U10-GPIO7-Pad16)") (class "Default")
      (node (ref "U10") (pin "16") (pinfunction "GPIO7_16") (pintype "bidirectional"))
    )
    (net (code "109") (name "unconnected-(U10-GPIO8{slash}UART_RX-Pad5)") (class "Default")
      (node (ref "U10") (pin "5") (pinfunction "GPIO8/UART_RX_5") (pintype "bidirectional"))
    )
    (net (code "110") (name "unconnected-(U10-GPIO9{slash}UART_TX-Pad6)") (class "Default")
      (node (ref "U10") (pin "6") (pinfunction "GPIO9/UART_TX_6") (pintype "bidirectional"))
    )
    (net (code "111") (name "unconnected-(U10-JTAG_TCK-Pad25)") (class "Default")
      (node (ref "U10") (pin "25") (pinfunction "JTAG_TCK_25") (pintype "input"))
    )
    (net (code "112") (name "unconnected-(U10-JTAG_TDI-Pad26)") (class "Default")
      (node (ref "U10") (pin "26") (pinfunction "JTAG_TDI_26") (pintype "input"))
    )
    (net (code "113") (name "unconnected-(U10-JTAG_TDO-Pad27)") (class "Default")
      (node (ref "U10") (pin "27") (pinfunction "JTAG_TDO_27") (pintype "output"))
    )
    (net (code "114") (name "unconnected-(U10-JTAG_TMS-Pad28)") (class "Default")
      (node (ref "U10") (pin "28") (pinfunction "JTAG_TMS_28") (pintype "input"))
    )
    (net (code "115") (name "unconnected-(U10-JTAG_TRSTZ-Pad29)") (class "Default")
      (node (ref "U10") (pin "29") (pinfunction "JTAG_TRSTZ_29") (pintype "input"))
    )
    (net (code "116") (name "unconnected-(U10-SPI_CS0-Pad21)") (class "Default")
      (node (ref "U10") (pin "21") (pinfunction "SPI_CS0_21") (pintype "output"))
    )
    (net (code "117") (name "unconnected-(U10-SPI_CS1{slash}GPIO10-Pad22)") (class "Default")
      (node (ref "U10") (pin "22") (pinfunction "SPI_CS1/GPIO10_22") (pintype "bidirectional"))
    )
    (net (code "118") (name "unconnected-(U10-SPI_CS2{slash}GPIO11-Pad23)") (class "Default")
      (node (ref "U10") (pin "23") (pinfunction "SPI_CS2/GPIO11_23") (pintype "bidirectional"))
    )
    (net (code "119") (name "unconnected-(U10-SPI_DATA_IN-Pad20)") (class "Default")
      (node (ref "U10") (pin "20") (pinfunction "SPI_DATA_IN_20") (pintype "input"))
    )
    (net (code "120") (name "unconnected-(U10-SPI_DATA_OUT-Pad18)") (class "Default")
      (node (ref "U10") (pin "18") (pinfunction "SPI_DATA_OUT_18") (pintype "output"))
    )
    (net (code "121") (name "unconnected-(U10-SPI_SCLK-Pad17)") (class "Default")
      (node (ref "U10") (pin "17") (pinfunction "SPI_SCLK_17") (pintype "output"))
    )
    (net (code "122") (name "unconnected-(U10-VSSOSC-Pad53)") (class "Default")
      (node (ref "U10") (pin "53") (pinfunction "VSSOSC_53") (pintype "power_in"))
    )
    (net (code "123") (name "unconnected-(U15-GPIO0-Pad8)") (class "Default")
      (node (ref "U15") (pin "8") (pinfunction "GPIO0_8") (pintype "bidirectional"))
    )
    (net (code "124") (name "unconnected-(U15-GPIO1-Pad9)") (class "Default")
      (node (ref "U15") (pin "9") (pinfunction "GPIO1_9") (pintype "bidirectional"))
    )
    (net (code "125") (name "unconnected-(U15-GPIO2-Pad10)") (class "Default")
      (node (ref "U15") (pin "10") (pinfunction "GPIO2_10") (pintype "bidirectional"))
    )
    (net (code "126") (name "unconnected-(U15-GPIO3-Pad11)") (class "Default")
      (node (ref "U15") (pin "11") (pinfunction "GPIO3_11") (pintype "bidirectional"))
    )
    (net (code "127") (name "unconnected-(U15-GPIO4-Pad13)") (class "Default")
      (node (ref "U15") (pin "13") (pinfunction "GPIO4_13") (pintype "bidirectional"))
    )
    (net (code "128") (name "unconnected-(U15-GPIO5-Pad14)") (class "Default")
      (node (ref "U15") (pin "14") (pinfunction "GPIO5_14") (pintype "bidirectional"))
    )
    (net (code "129") (name "unconnected-(U15-GPIO6-Pad15)") (class "Default")
      (node (ref "U15") (pin "15") (pinfunction "GPIO6_15") (pintype "bidirectional"))
    )
    (net (code "130") (name "unconnected-(U15-GPIO7-Pad16)") (class "Default")
      (node (ref "U15") (pin "16") (pinfunction "GPIO7_16") (pintype "bidirectional"))
    )
    (net (code "131") (name "unconnected-(U15-GPIO8{slash}UART_RX-Pad5)") (class "Default")
      (node (ref "U15") (pin "5") (pinfunction "GPIO8/UART_RX_5") (pintype "bidirectional"))
    )
    (net (code "132") (name "unconnected-(U15-GPIO9{slash}UART_TX-Pad6)") (class "Default")
      (node (ref "U15") (pin "6") (pinfunction "GPIO9/UART_TX_6") (pintype "bidirectional"))
    )
    (net (code "133") (name "unconnected-(U15-JTAG_TCK-Pad25)") (class "Default")
      (node (ref "U15") (pin "25") (pinfunction "JTAG_TCK_25") (pintype "input"))
    )
    (net (code "134") (name "unconnected-(U15-JTAG_TDI-Pad26)") (class "Default")
      (node (ref "U15") (pin "26") (pinfunction "JTAG_TDI_26") (pintype "input"))
    )
    (net (code "135") (name "unconnected-(U15-JTAG_TDO-Pad27)") (class "Default")
      (node (ref "U15") (pin "27") (pinfunction "JTAG_TDO_27") (pintype "output"))
    )
    (net (code "136") (name "unconnected-(U15-JTAG_TMS-Pad28)") (class "Default")
      (node (ref "U15") (pin "28") (pinfunction "JTAG_TMS_28") (pintype "input"))
    )
    (net (code "137") (name "unconnected-(U15-JTAG_TRSTZ-Pad29)") (class "Default")
      (node (ref "U15") (pin "29") (pinfunction "JTAG_TRSTZ_29") (pintype "input"))
    )
    (net (code "138") (name "unconnected-(U15-SPI_CS0-Pad21)") (class "Default")
      (node (ref "U15") (pin "21") (pinfunction "SPI_CS0_21") (pintype "output"))
    )
    (net (code "139") (name "unconnected-(U15-SPI_CS1{slash}GPIO10-Pad22)") (class "Default")
      (node (ref "U15") (pin "22") (pinfunction "SPI_CS1/GPIO10_22") (pintype "bidirectional"))
    )
    (net (code "140") (name "unconnected-(U15-SPI_CS2{slash}GPIO11-Pad23)") (class "Default")
      (node (ref "U15") (pin "23") (pinfunction "SPI_CS2/GPIO11_23") (pintype "bidirectional"))
    )
    (net (code "141") (name "unconnected-(U15-SPI_DATA_IN-Pad20)") (class "Default")
      (node (ref "U15") (pin "20") (pinfunction "SPI_DATA_IN_20") (pintype "input"))
    )
    (net (code "142") (name "unconnected-(U15-SPI_DATA_OUT-Pad18)") (class "Default")
      (node (ref "U15") (pin "18") (pinfunction "SPI_DATA_OUT_18") (pintype "output"))
    )
    (net (code "143") (name "unconnected-(U15-SPI_SCLK-Pad17)") (class "Default")
      (node (ref "U15") (pin "17") (pinfunction "SPI_SCLK_17") (pintype "output"))
    )
    (net (code "144") (name "unconnected-(U15-VSSOSC-Pad53)") (class "Default")
      (node (ref "U15") (pin "53") (pinfunction "VSSOSC_53") (pintype "power_in"))
    )
  )
)
